# frontplatine_v0_2_310121.net
KiCad netlist of a schematic drawn in EAGLE
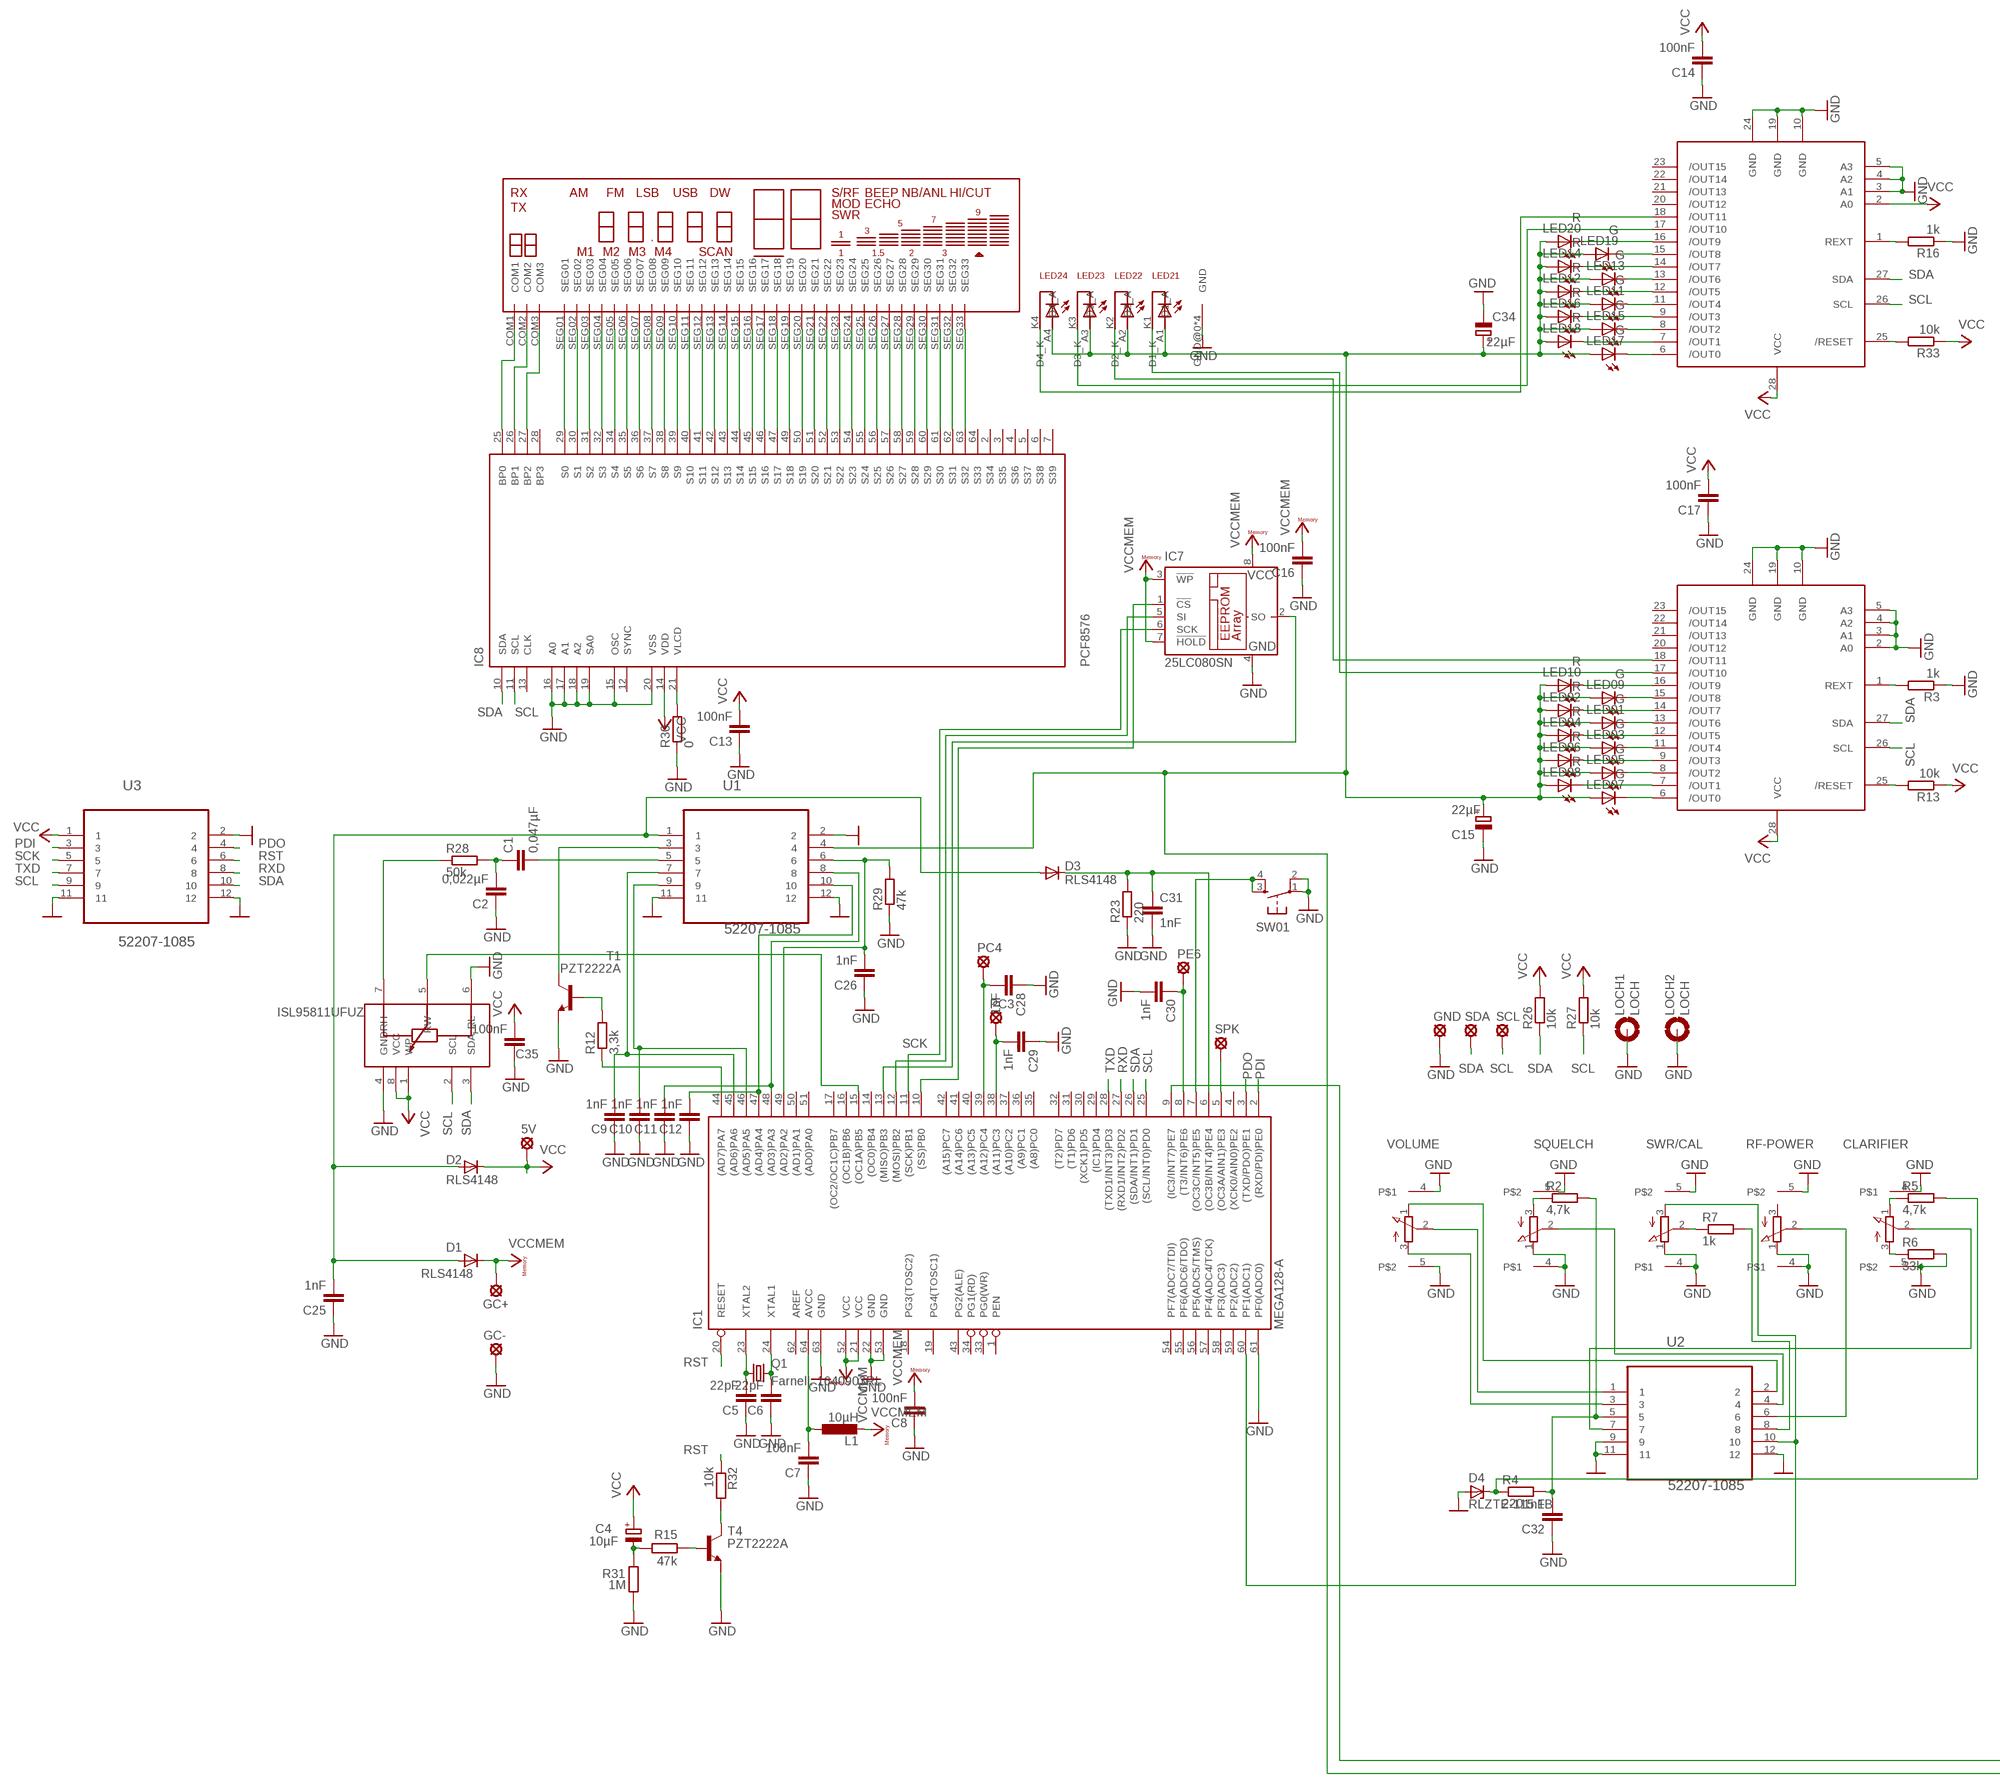
[diagram p0: schematic, sheet 1, part 1 of 2]
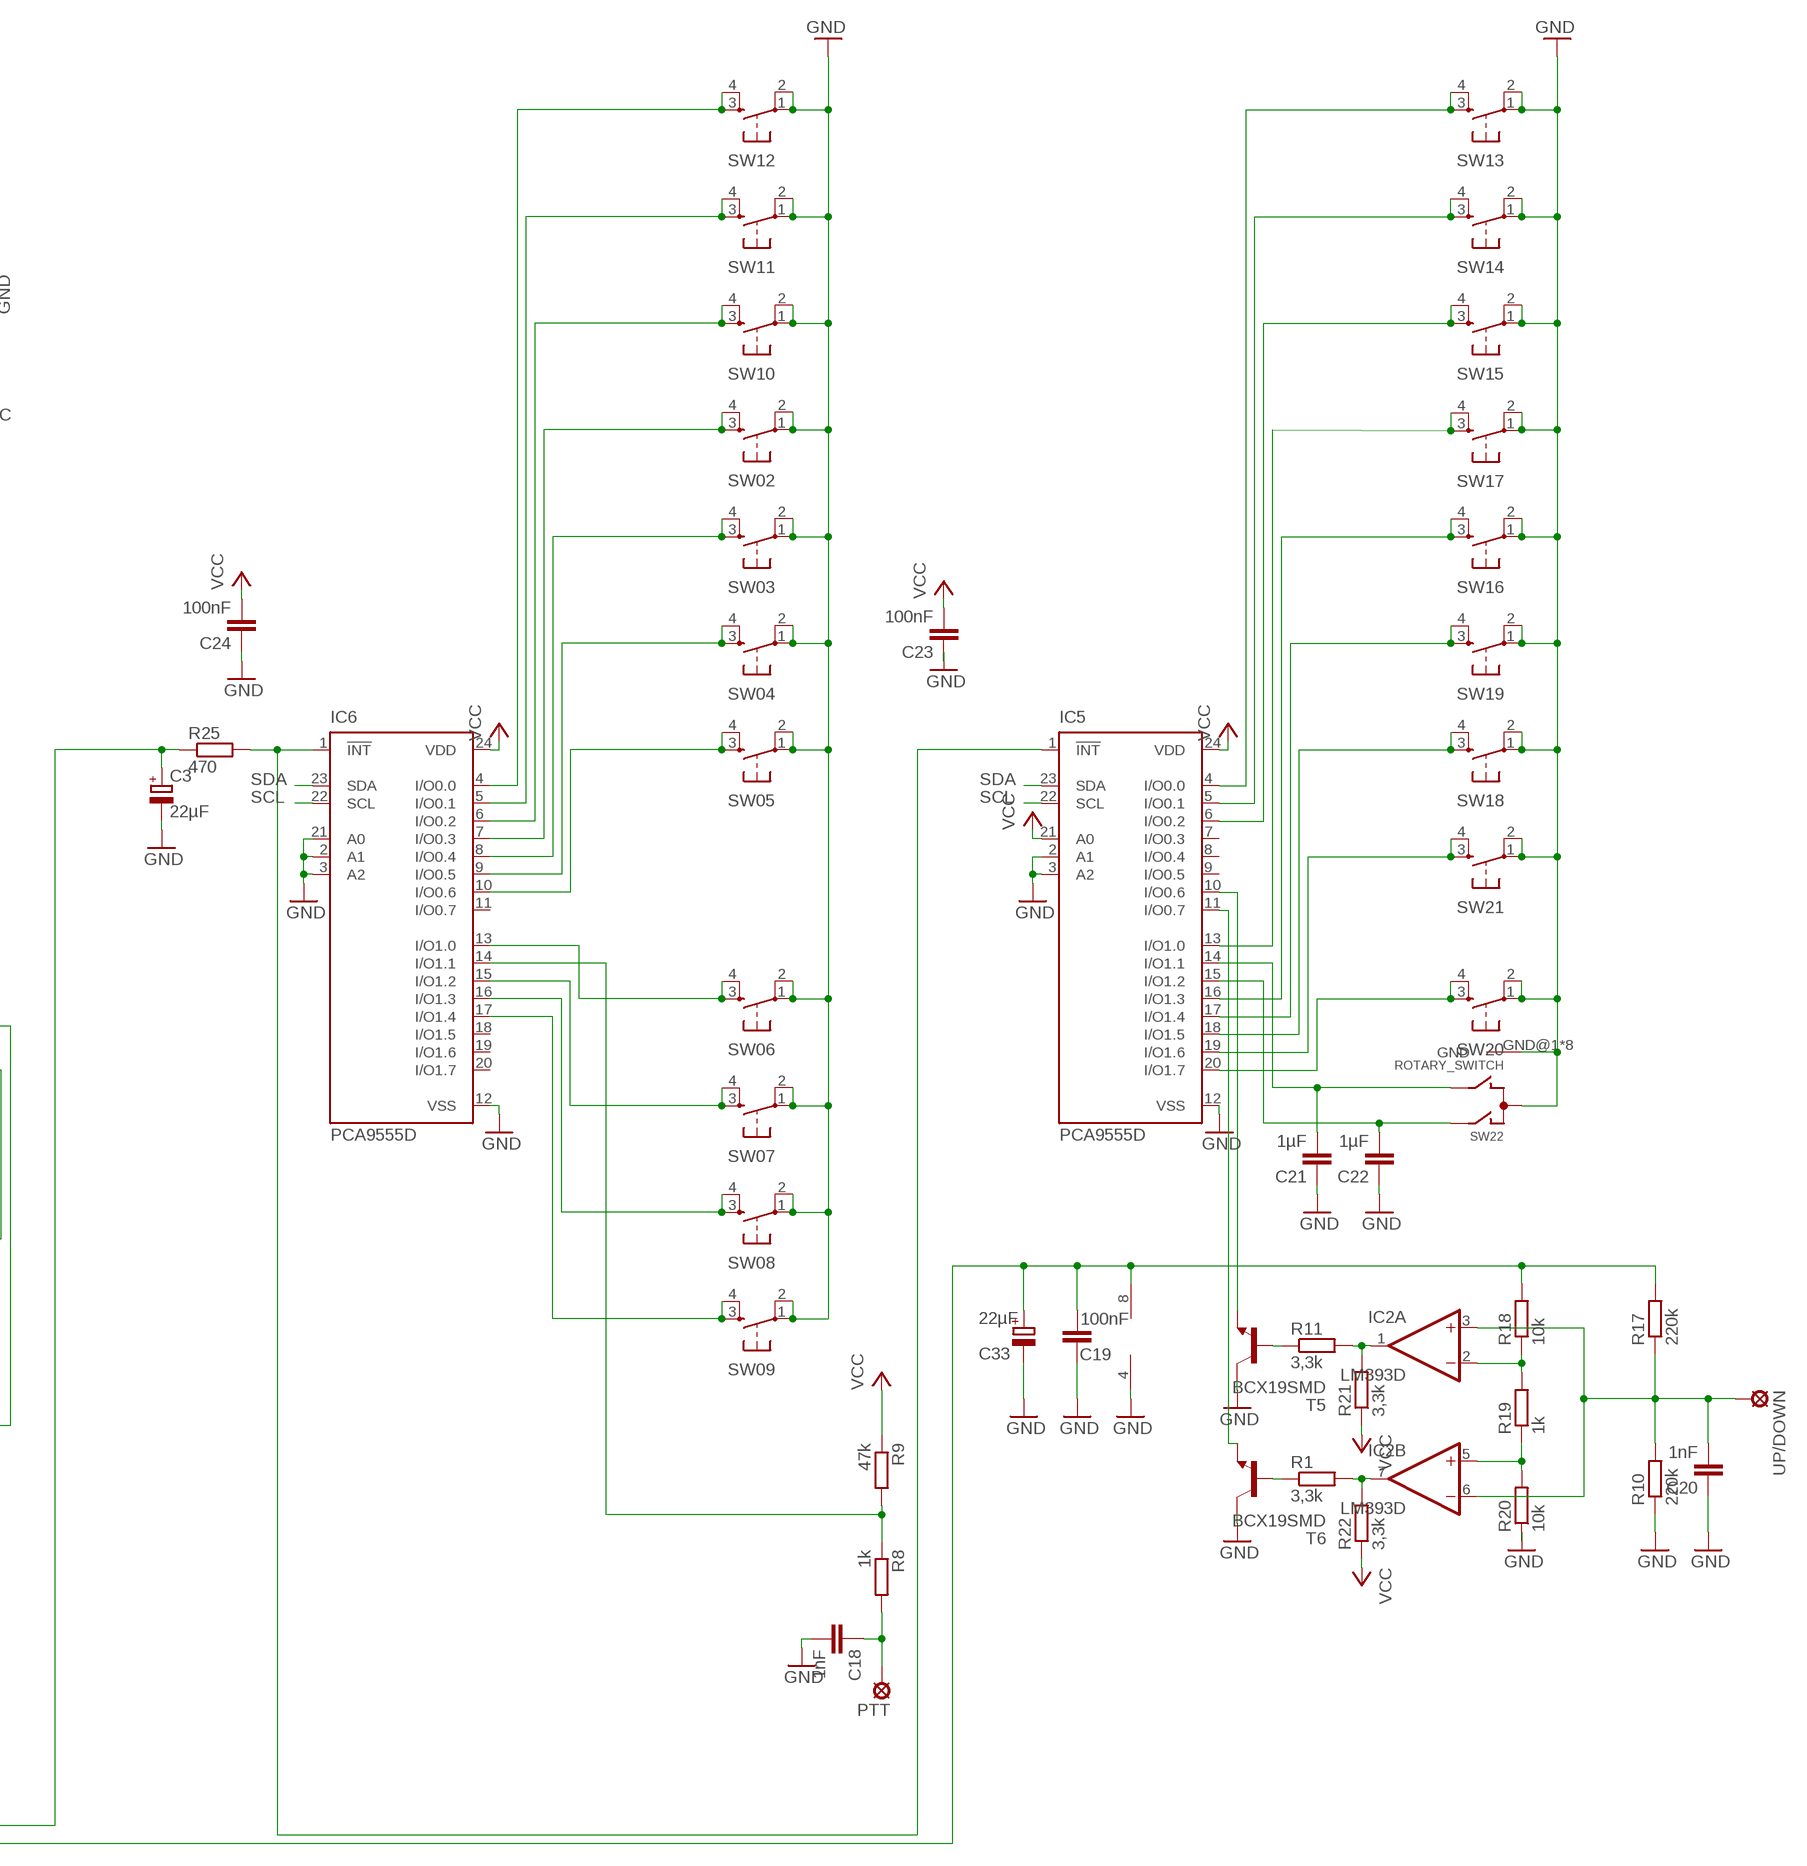
[diagram p1: schematic, sheet 1, part 2 of 2]

(export (version "E")
  (design (tool "Eeschema 10.0.6"))
  (components
    (comp (ref "5V")
      (value "SE11")
      (footprint "eagle-import:SE11")
      (libsource (lib "eagle-import") (part "SE11"))
    )
    (comp (ref "C1")
      (value "0,047µF")
      (footprint "eagle-import:C1206")
      (libsource (lib "eagle-import") (part "C-EUC1206"))
    )
    (comp (ref "C2")
      (value "0,022µF")
      (footprint "eagle-import:C1206")
      (libsource (lib "eagle-import") (part "resistor_C-EUC1206"))
    )
    (comp (ref "C3")
      (value "22µF")
      (footprint "eagle-import:CT3216")
      (libsource (lib "eagle-import") (part "CPOL-EUCT3216"))
    )
    (comp (ref "C4")
      (value "10µF")
      (footprint "eagle-import:CT3216")
      (libsource (lib "eagle-import") (part "CPOL-EUCT3216"))
    )
    (comp (ref "C5")
      (value "22pF")
      (footprint "eagle-import:C1206")
      (libsource (lib "eagle-import") (part "resistor_C-EUC1206"))
    )
    (comp (ref "C6")
      (value "22pF")
      (footprint "eagle-import:C1206")
      (libsource (lib "eagle-import") (part "resistor_C-EUC1206"))
    )
    (comp (ref "C7")
      (value "100nF")
      (footprint "eagle-import:C1206")
      (libsource (lib "eagle-import") (part "resistor_C-EUC1206"))
    )
    (comp (ref "C8")
      (value "100nF")
      (footprint "eagle-import:C1206")
      (libsource (lib "eagle-import") (part "resistor_C-EUC1206"))
    )
    (comp (ref "C9")
      (value "1nF")
      (footprint "eagle-import:C1206")
      (libsource (lib "eagle-import") (part "resistor_C-EUC1206"))
    )
    (comp (ref "C10")
      (value "1nF")
      (footprint "eagle-import:C1206")
      (libsource (lib "eagle-import") (part "resistor_C-EUC1206"))
    )
    (comp (ref "C11")
      (value "1nF")
      (footprint "eagle-import:C1206")
      (libsource (lib "eagle-import") (part "resistor_C-EUC1206"))
    )
    (comp (ref "C12")
      (value "1nF")
      (footprint "eagle-import:C1206")
      (libsource (lib "eagle-import") (part "resistor_C-EUC1206"))
    )
    (comp (ref "C13")
      (value "100nF")
      (footprint "eagle-import:C1206")
      (libsource (lib "eagle-import") (part "resistor_C-EUC1206"))
    )
    (comp (ref "C14")
      (value "100nF")
      (footprint "eagle-import:C1206")
      (libsource (lib "eagle-import") (part "resistor_C-EUC1206"))
    )
    (comp (ref "C15")
      (value "22µF")
      (footprint "eagle-import:CT3216")
      (libsource (lib "eagle-import") (part "CPOL-EUCT3216"))
    )
    (comp (ref "C16")
      (value "100nF")
      (footprint "eagle-import:C1206")
      (libsource (lib "eagle-import") (part "resistor_C-EUC1206"))
    )
    (comp (ref "C17")
      (value "100nF")
      (footprint "eagle-import:C1206")
      (libsource (lib "eagle-import") (part "resistor_C-EUC1206"))
    )
    (comp (ref "C18")
      (value "1nF")
      (footprint "eagle-import:C1206")
      (libsource (lib "eagle-import") (part "resistor_C-EUC1206"))
    )
    (comp (ref "C19")
      (value "100nF")
      (footprint "eagle-import:C1206")
      (libsource (lib "eagle-import") (part "resistor_C-EUC1206"))
    )
    (comp (ref "C20")
      (value "1nF")
      (footprint "eagle-import:C1206")
      (libsource (lib "eagle-import") (part "resistor_C-EUC1206"))
    )
    (comp (ref "C21")
      (value "1µF")
      (footprint "eagle-import:C1206")
      (libsource (lib "eagle-import") (part "resistor_C-EUC1206"))
    )
    (comp (ref "C22")
      (value "1µF")
      (footprint "eagle-import:C1206")
      (libsource (lib "eagle-import") (part "resistor_C-EUC1206"))
    )
    (comp (ref "C23")
      (value "100nF")
      (footprint "eagle-import:C1206")
      (libsource (lib "eagle-import") (part "resistor_C-EUC1206"))
    )
    (comp (ref "C24")
      (value "100nF")
      (footprint "eagle-import:C1206")
      (libsource (lib "eagle-import") (part "resistor_C-EUC1206"))
    )
    (comp (ref "C25")
      (value "1nF")
      (footprint "eagle-import:C1206")
      (libsource (lib "eagle-import") (part "resistor_C-EUC1206"))
    )
    (comp (ref "C26")
      (value "1nF")
      (footprint "eagle-import:C1206")
      (libsource (lib "eagle-import") (part "resistor_C-EUC1206"))
    )
    (comp (ref "C28")
      (value "1nF")
      (footprint "eagle-import:C1206")
      (libsource (lib "eagle-import") (part "resistor_C-EUC1206"))
    )
    (comp (ref "C29")
      (value "1nF")
      (footprint "eagle-import:C1206")
      (libsource (lib "eagle-import") (part "resistor_C-EUC1206"))
    )
    (comp (ref "C30")
      (value "1nF")
      (footprint "eagle-import:C1206")
      (libsource (lib "eagle-import") (part "resistor_C-EUC1206"))
    )
    (comp (ref "C31")
      (value "1nF")
      (footprint "eagle-import:C1206")
      (libsource (lib "eagle-import") (part "resistor_C-EUC1206"))
    )
    (comp (ref "C32")
      (value "1nF")
      (footprint "eagle-import:C1206")
      (libsource (lib "eagle-import") (part "resistor_C-EUC1206"))
    )
    (comp (ref "C33")
      (value "22µF")
      (footprint "eagle-import:CT3216")
      (libsource (lib "eagle-import") (part "CPOL-EUCT3216"))
    )
    (comp (ref "C34")
      (value "22µF")
      (footprint "eagle-import:CT3216")
      (libsource (lib "eagle-import") (part "CPOL-EUCT3216"))
    )
    (comp (ref "C35")
      (value "100nF")
      (footprint "eagle-import:C1206")
      (libsource (lib "eagle-import") (part "resistor_C-EUC1206"))
    )
    (comp (ref "CLARIFIER")
      (value "POTI")
      (footprint "eagle-import:POTI")
      (libsource (lib "eagle-import") (part "POTI"))
    )
    (comp (ref "D1")
      (value "RLS4148")
      (footprint "eagle-import:SOD80C")
      (libsource (lib "eagle-import") (part "DIODE-SOD80C"))
    )
    (comp (ref "D2")
      (value "RLS4148")
      (footprint "eagle-import:SOD80C")
      (libsource (lib "eagle-import") (part "DIODE-SOD80C"))
    )
    (comp (ref "D3")
      (value "RLS4148")
      (footprint "eagle-import:SOD80C")
      (libsource (lib "eagle-import") (part "DIODE-SOD80C"))
    )
    (comp (ref "D4")
      (value "RLZTE-115.1B")
      (footprint "eagle-import:SOD80C")
      (libsource (lib "eagle-import") (part "ZENER-DIODESOD80C"))
    )
    (comp (ref "DISPLAY1")
      (value "DISPLAY")
      (footprint "eagle-import:DISPLAY")
      (libsource (lib "eagle-import") (part "DISPLAY"))
    )
    (comp (ref "GC+")
      (value "SE11")
      (footprint "eagle-import:SE11")
      (libsource (lib "eagle-import") (part "SE11"))
    )
    (comp (ref "GC-")
      (value "SE11")
      (footprint "eagle-import:SE11")
      (libsource (lib "eagle-import") (part "SE11"))
    )
    (comp (ref "GND")
      (value "SE11")
      (footprint "eagle-import:SE11")
      (libsource (lib "eagle-import") (part "SE11"))
    )
    (comp (ref "IC1")
      (value "MEGA128-A")
      (footprint "eagle-import:TQFP64")
      (fields (field (name "MPN") "ATMEGA128-16AU"))
      (libsource (lib "eagle-import") (part "MEGA128-A"))
    )
    (comp (ref "IC2")
      (value "LM393D")
      (footprint "eagle-import:SO08")
      (libsource (lib "eagle-import") (part "LM393D"))
    )
    (comp (ref "IC3")
      (value "TLC59116")
      (footprint "eagle-import:TSSOP28")
      (libsource (lib "eagle-import") (part "TLC59116"))
    )
    (comp (ref "IC4")
      (value "TLC59116")
      (footprint "eagle-import:TSSOP28")
      (libsource (lib "eagle-import") (part "TLC59116"))
    )
    (comp (ref "IC5")
      (value "PCA9555D")
      (footprint "eagle-import:SO24")
      (fields (field (name "MPN") "PCA9555DW"))
      (libsource (lib "eagle-import") (part "PCA9555D"))
    )
    (comp (ref "IC6")
      (value "PCA9555D")
      (footprint "eagle-import:SO24")
      (fields (field (name "MPN") "PCA9555DW"))
      (libsource (lib "eagle-import") (part "PCA9555D"))
    )
    (comp (ref "IC7")
      (value "25LC080SN")
      (footprint "eagle-import:SO-08")
      (fields
        (field (name "MF") "MICROCHIP")
        (field (name "MPN") "25LC080/SN")
        (field (name "MPN_1") "25LC080/SN")
        (field (name "OC_FARNELL") "1137302")
        (field (name "OC_NEWARK") "96K4092")
      )
      (libsource (lib "eagle-import") (part "25SNLC080"))
    )
    (comp (ref "IC8")
      (value "PCF8576")
      (footprint "eagle-import:LQFP-ST-64-2")
      (libsource (lib "eagle-import") (part "PCF8576"))
    )
    (comp (ref "IC9")
      (value "ISL95811UFUZ")
      (footprint "eagle-import:MSOP8")
      (libsource (lib "eagle-import") (part "ISL95811UFUZ"))
    )
    (comp (ref "L1")
      (value "10µH")
      (footprint "eagle-import:L1812")
      (libsource (lib "eagle-import") (part "L-EUL1812"))
    )
    (comp (ref "LED01")
      (value "G")
      (footprint "eagle-import:CHIPLED_1206")
      (libsource (lib "eagle-import") (part "LEDCHIPLED_1206"))
    )
    (comp (ref "LED02")
      (value "R")
      (footprint "eagle-import:CHIPLED_1206")
      (libsource (lib "eagle-import") (part "LEDCHIPLED_1206"))
    )
    (comp (ref "LED03")
      (value "G")
      (footprint "eagle-import:CHIPLED_1206")
      (libsource (lib "eagle-import") (part "LEDCHIPLED_1206"))
    )
    (comp (ref "LED04")
      (value "R")
      (footprint "eagle-import:CHIPLED_1206")
      (libsource (lib "eagle-import") (part "LEDCHIPLED_1206"))
    )
    (comp (ref "LED05")
      (value "G")
      (footprint "eagle-import:CHIPLED_1206")
      (libsource (lib "eagle-import") (part "LEDCHIPLED_1206"))
    )
    (comp (ref "LED06")
      (value "R")
      (footprint "eagle-import:CHIPLED_1206")
      (libsource (lib "eagle-import") (part "LEDCHIPLED_1206"))
    )
    (comp (ref "LED07")
      (value "G")
      (footprint "eagle-import:CHIPLED_1206")
      (libsource (lib "eagle-import") (part "LEDCHIPLED_1206"))
    )
    (comp (ref "LED08")
      (value "R")
      (footprint "eagle-import:CHIPLED_1206")
      (libsource (lib "eagle-import") (part "LEDCHIPLED_1206"))
    )
    (comp (ref "LED09")
      (value "G")
      (footprint "eagle-import:CHIPLED_1206")
      (libsource (lib "eagle-import") (part "LEDCHIPLED_1206"))
    )
    (comp (ref "LED10")
      (value "R")
      (footprint "eagle-import:CHIPLED_1206")
      (libsource (lib "eagle-import") (part "LEDCHIPLED_1206"))
    )
    (comp (ref "LED11")
      (value "G")
      (footprint "eagle-import:CHIPLED_1206")
      (libsource (lib "eagle-import") (part "LEDCHIPLED_1206"))
    )
    (comp (ref "LED12")
      (value "R")
      (footprint "eagle-import:CHIPLED_1206")
      (libsource (lib "eagle-import") (part "LEDCHIPLED_1206"))
    )
    (comp (ref "LED13")
      (value "G")
      (footprint "eagle-import:CHIPLED_1206")
      (libsource (lib "eagle-import") (part "LEDCHIPLED_1206"))
    )
    (comp (ref "LED14")
      (value "R")
      (footprint "eagle-import:CHIPLED_1206")
      (libsource (lib "eagle-import") (part "LEDCHIPLED_1206"))
    )
    (comp (ref "LED15")
      (value "G")
      (footprint "eagle-import:CHIPLED_1206")
      (libsource (lib "eagle-import") (part "LEDCHIPLED_1206"))
    )
    (comp (ref "LED16")
      (value "R")
      (footprint "eagle-import:CHIPLED_1206")
      (libsource (lib "eagle-import") (part "LEDCHIPLED_1206"))
    )
    (comp (ref "LED17")
      (value "G")
      (footprint "eagle-import:CHIPLED_1206")
      (libsource (lib "eagle-import") (part "LEDCHIPLED_1206"))
    )
    (comp (ref "LED18")
      (value "R")
      (footprint "eagle-import:CHIPLED_1206")
      (libsource (lib "eagle-import") (part "LEDCHIPLED_1206"))
    )
    (comp (ref "LED19")
      (value "G")
      (footprint "eagle-import:CHIPLED_1206")
      (libsource (lib "eagle-import") (part "LEDCHIPLED_1206"))
    )
    (comp (ref "LED20")
      (value "R")
      (footprint "eagle-import:CHIPLED_1206")
      (libsource (lib "eagle-import") (part "LEDCHIPLED_1206"))
    )
    (comp (ref "LOCH1")
      (value "LOCH")
      (footprint "eagle-import:LOCH")
      (libsource (lib "eagle-import") (part "LOCH"))
    )
    (comp (ref "LOCH2")
      (value "LOCH")
      (footprint "eagle-import:LOCH")
      (libsource (lib "eagle-import") (part "LOCH"))
    )
    (comp (ref "PC3")
      (value "SE11")
      (footprint "eagle-import:SE11")
      (libsource (lib "eagle-import") (part "SE11"))
    )
    (comp (ref "PC4")
      (value "SE11")
      (footprint "eagle-import:SE11")
      (libsource (lib "eagle-import") (part "SE11"))
    )
    (comp (ref "PE6")
      (value "SE11")
      (footprint "eagle-import:SE11")
      (libsource (lib "eagle-import") (part "SE11"))
    )
    (comp (ref "PTT")
      (value "SE11")
      (footprint "eagle-import:SE11")
      (libsource (lib "eagle-import") (part "SE11"))
    )
    (comp (ref "Q1")
      (value "Farnell: 1640903RL")
      (footprint "eagle-import:HC49UP")
      (libsource (lib "eagle-import") (part "CRYSTALHC49UP"))
    )
    (comp (ref "R1")
      (value "3,3k")
      (footprint "eagle-import:R1206")
      (libsource (lib "eagle-import") (part "resistor_R-EU_R1206"))
    )
    (comp (ref "R2")
      (value "4,7k")
      (footprint "eagle-import:R1206")
      (libsource (lib "eagle-import") (part "resistor_R-EU_R1206"))
    )
    (comp (ref "R3")
      (value "1k")
      (footprint "eagle-import:R1206")
      (libsource (lib "eagle-import") (part "R-EU_R1206"))
    )
    (comp (ref "R4")
      (value "220")
      (footprint "eagle-import:R1206")
      (libsource (lib "eagle-import") (part "resistor_R-EU_R1206"))
    )
    (comp (ref "R5")
      (value "4,7k")
      (footprint "eagle-import:R1206")
      (libsource (lib "eagle-import") (part "resistor_R-EU_R1206"))
    )
    (comp (ref "R6")
      (value "33k")
      (footprint "eagle-import:R1206")
      (libsource (lib "eagle-import") (part "resistor_R-EU_R1206"))
    )
    (comp (ref "R7")
      (value "1k")
      (footprint "eagle-import:R1206")
      (libsource (lib "eagle-import") (part "resistor_R-EU_R1206"))
    )
    (comp (ref "R8")
      (value "1k")
      (footprint "eagle-import:R1206")
      (libsource (lib "eagle-import") (part "resistor_R-EU_R1206"))
    )
    (comp (ref "R9")
      (value "47k")
      (footprint "eagle-import:R1206")
      (libsource (lib "eagle-import") (part "resistor_R-EU_R1206"))
    )
    (comp (ref "R10")
      (value "220k")
      (footprint "eagle-import:R1206")
      (libsource (lib "eagle-import") (part "resistor_R-EU_R1206"))
    )
    (comp (ref "R11")
      (value "3,3k")
      (footprint "eagle-import:R1206")
      (libsource (lib "eagle-import") (part "resistor_R-EU_R1206"))
    )
    (comp (ref "R12")
      (value "3,3k")
      (footprint "eagle-import:R1206")
      (libsource (lib "eagle-import") (part "resistor_R-EU_R1206"))
    )
    (comp (ref "R13")
      (value "10k")
      (footprint "eagle-import:R1206")
      (libsource (lib "eagle-import") (part "resistor_R-EU_R1206"))
    )
    (comp (ref "R15")
      (value "47k")
      (footprint "eagle-import:R1206")
      (libsource (lib "eagle-import") (part "resistor_R-EU_R1206"))
    )
    (comp (ref "R16")
      (value "1k")
      (footprint "eagle-import:R1206")
      (libsource (lib "eagle-import") (part "R-EU_R1206"))
    )
    (comp (ref "R17")
      (value "220k")
      (footprint "eagle-import:R1206")
      (libsource (lib "eagle-import") (part "resistor_R-EU_R1206"))
    )
    (comp (ref "R18")
      (value "10k")
      (footprint "eagle-import:R1206")
      (libsource (lib "eagle-import") (part "resistor_R-EU_R1206"))
    )
    (comp (ref "R19")
      (value "1k")
      (footprint "eagle-import:R1206")
      (libsource (lib "eagle-import") (part "resistor_R-EU_R1206"))
    )
    (comp (ref "R20")
      (value "10k")
      (footprint "eagle-import:R1206")
      (libsource (lib "eagle-import") (part "resistor_R-EU_R1206"))
    )
    (comp (ref "R21")
      (value "3,3k")
      (footprint "eagle-import:R1206")
      (libsource (lib "eagle-import") (part "resistor_R-EU_R1206"))
    )
    (comp (ref "R22")
      (value "3,3k")
      (footprint "eagle-import:R1206")
      (libsource (lib "eagle-import") (part "resistor_R-EU_R1206"))
    )
    (comp (ref "R23")
      (value "220")
      (footprint "eagle-import:R1206")
      (libsource (lib "eagle-import") (part "resistor_R-EU_R1206"))
    )
    (comp (ref "R25")
      (value "470")
      (footprint "eagle-import:R1206")
      (libsource (lib "eagle-import") (part "resistor_R-EU_R1206"))
    )
    (comp (ref "R26")
      (value "10k")
      (footprint "eagle-import:R1206")
      (libsource (lib "eagle-import") (part "resistor_R-EU_R1206"))
    )
    (comp (ref "R27")
      (value "10k")
      (footprint "eagle-import:R1206")
      (libsource (lib "eagle-import") (part "resistor_R-EU_R1206"))
    )
    (comp (ref "R28")
      (value "50k")
      (footprint "eagle-import:R1206")
      (libsource (lib "eagle-import") (part "resistor_R-EU_R1206"))
    )
    (comp (ref "R29")
      (value "47k")
      (footprint "eagle-import:R1206")
      (libsource (lib "eagle-import") (part "resistor_R-EU_R1206"))
    )
    (comp (ref "R30")
      (value "0")
      (footprint "eagle-import:R1206")
      (libsource (lib "eagle-import") (part "resistor_R-EU_R1206"))
    )
    (comp (ref "R31")
      (value "1M")
      (footprint "eagle-import:R1206")
      (libsource (lib "eagle-import") (part "resistor_R-EU_R1206"))
    )
    (comp (ref "R32")
      (value "10k")
      (footprint "eagle-import:R1206")
      (libsource (lib "eagle-import") (part "resistor_R-EU_R1206"))
    )
    (comp (ref "R33")
      (value "10k")
      (footprint "eagle-import:R1206")
      (libsource (lib "eagle-import") (part "resistor_R-EU_R1206"))
    )
    (comp (ref "RF-POWER")
      (value "POTI")
      (footprint "eagle-import:POTI")
      (libsource (lib "eagle-import") (part "POTI"))
    )
    (comp (ref "SCL")
      (value "SE11")
      (footprint "eagle-import:SE11")
      (libsource (lib "eagle-import") (part "SE11"))
    )
    (comp (ref "SDA")
      (value "SE11")
      (footprint "eagle-import:SE11")
      (libsource (lib "eagle-import") (part "SE11"))
    )
    (comp (ref "SPK")
      (value "SE11")
      (footprint "eagle-import:SE11")
      (libsource (lib "eagle-import") (part "SE11"))
    )
    (comp (ref "SQUELCH")
      (value "POTI")
      (footprint "eagle-import:POTI")
      (libsource (lib "eagle-import") (part "POTI"))
    )
    (comp (ref "SW01")
      (value "TASTER")
      (footprint "eagle-import:TASTER")
      (libsource (lib "eagle-import") (part "TASTER"))
    )
    (comp (ref "SW02")
      (value "TASTER")
      (footprint "eagle-import:TASTER")
      (libsource (lib "eagle-import") (part "TASTER"))
    )
    (comp (ref "SW03")
      (value "TASTER")
      (footprint "eagle-import:TASTER")
      (libsource (lib "eagle-import") (part "TASTER"))
    )
    (comp (ref "SW04")
      (value "TASTER")
      (footprint "eagle-import:TASTER")
      (libsource (lib "eagle-import") (part "TASTER"))
    )
    (comp (ref "SW05")
      (value "TASTER")
      (footprint "eagle-import:TASTER")
      (libsource (lib "eagle-import") (part "TASTER"))
    )
    (comp (ref "SW06")
      (value "TASTER")
      (footprint "eagle-import:TASTER")
      (libsource (lib "eagle-import") (part "TASTER"))
    )
    (comp (ref "SW07")
      (value "TASTER")
      (footprint "eagle-import:TASTER")
      (libsource (lib "eagle-import") (part "TASTER"))
    )
    (comp (ref "SW08")
      (value "TASTER")
      (footprint "eagle-import:TASTER")
      (libsource (lib "eagle-import") (part "TASTER"))
    )
    (comp (ref "SW09")
      (value "TASTER")
      (footprint "eagle-import:TASTER")
      (libsource (lib "eagle-import") (part "TASTER"))
    )
    (comp (ref "SW10")
      (value "TASTER")
      (footprint "eagle-import:TASTER")
      (libsource (lib "eagle-import") (part "TASTER"))
    )
    (comp (ref "SW11")
      (value "TASTER")
      (footprint "eagle-import:TASTER")
      (libsource (lib "eagle-import") (part "TASTER"))
    )
    (comp (ref "SW12")
      (value "TASTER")
      (footprint "eagle-import:TASTER")
      (libsource (lib "eagle-import") (part "TASTER"))
    )
    (comp (ref "SW13")
      (value "TASTER")
      (footprint "eagle-import:TASTER")
      (libsource (lib "eagle-import") (part "TASTER"))
    )
    (comp (ref "SW14")
      (value "TASTER")
      (footprint "eagle-import:TASTER")
      (libsource (lib "eagle-import") (part "TASTER"))
    )
    (comp (ref "SW15")
      (value "TASTER")
      (footprint "eagle-import:TASTER")
      (libsource (lib "eagle-import") (part "TASTER"))
    )
    (comp (ref "SW16")
      (value "TASTER")
      (footprint "eagle-import:TASTER")
      (libsource (lib "eagle-import") (part "TASTER"))
    )
    (comp (ref "SW17")
      (value "TASTER")
      (footprint "eagle-import:TASTER")
      (libsource (lib "eagle-import") (part "TASTER"))
    )
    (comp (ref "SW18")
      (value "TASTER")
      (footprint "eagle-import:TASTER")
      (libsource (lib "eagle-import") (part "TASTER"))
    )
    (comp (ref "SW19")
      (value "TASTER")
      (footprint "eagle-import:TASTER")
      (libsource (lib "eagle-import") (part "TASTER"))
    )
    (comp (ref "SW20")
      (value "TASTER")
      (footprint "eagle-import:TASTER")
      (libsource (lib "eagle-import") (part "TASTER"))
    )
    (comp (ref "SW21")
      (value "TASTER")
      (footprint "eagle-import:TASTER")
      (libsource (lib "eagle-import") (part "TASTER"))
    )
    (comp (ref "SW22")
      (value "ROTARY_SWITCH")
      (footprint "eagle-import:ROTARY_SWITCH")
      (libsource (lib "eagle-import") (part "ROTARY_SWITCH"))
    )
    (comp (ref "SWR/CAL")
      (value "POTI")
      (footprint "eagle-import:POTI")
      (libsource (lib "eagle-import") (part "POTI"))
    )
    (comp (ref "T1")
      (value "PZT2222A")
      (footprint "eagle-import:SOT223")
      (libsource (lib "eagle-import") (part "-NPN-SOT223PZT2222A"))
    )
    (comp (ref "T4")
      (value "PZT2222A")
      (footprint "eagle-import:SOT223")
      (libsource (lib "eagle-import") (part "-NPN-SOT223PZT2222A"))
    )
    (comp (ref "T5")
      (value "BCX19SMD")
      (footprint "eagle-import:SOT23-BEC")
      (libsource (lib "eagle-import") (part "BCX19SMD"))
    )
    (comp (ref "T6")
      (value "BCX19SMD")
      (footprint "eagle-import:SOT23-BEC")
      (libsource (lib "eagle-import") (part "BCX19SMD"))
    )
    (comp (ref "U1")
      (value "52207-1085")
      (footprint "eagle-import:MOLEX_52207-1085")
      (fields
        (field (name "MPN") "52207-1085")
        (field (name "OC_FARNELL") "1079938")
        (field (name "OC_NEWARK") "58J9503")
        (field (name "PACKAGE") "SOCKET FPC, SMT, 1MM, 10 WAY")
      )
      (libsource (lib "eagle-import") (part "52207-1085"))
    )
    (comp (ref "U2")
      (value "52207-1085")
      (footprint "eagle-import:MOLEX_52207-1085")
      (fields
        (field (name "MPN") "52207-1085")
        (field (name "OC_FARNELL") "1079938")
        (field (name "OC_NEWARK") "58J9503")
        (field (name "PACKAGE") "SOCKET FPC, SMT, 1MM, 10 WAY")
      )
      (libsource (lib "eagle-import") (part "52207-1085"))
    )
    (comp (ref "U3")
      (value "52207-1085")
      (footprint "eagle-import:MOLEX_52207-1085")
      (libsource (lib "eagle-import") (part "52207-1085"))
    )
    (comp (ref "UP/DOWN")
      (value "SE11")
      (footprint "eagle-import:SE11")
      (libsource (lib "eagle-import") (part "SE11"))
    )
    (comp (ref "VOLUME")
      (value "POTI")
      (footprint "eagle-import:POTI")
      (libsource (lib "eagle-import") (part "POTI"))
    )
  )
  (nets
    (net (code "1") (name "/PDI") (class "Default")
      (node (ref "IC1") (pin "2") (pinfunction "(RXD/PDI)PE0_2") (pintype "bidirectional"))
      (node (ref "U3") (pin "3") (pinfunction "3_3") (pintype "passive"))
    )
    (net (code "2") (name "/PDO") (class "Default")
      (node (ref "IC1") (pin "3") (pinfunction "(TXD/PDO)PE1_3") (pintype "bidirectional"))
      (node (ref "U3") (pin "4") (pinfunction "4_4") (pintype "passive"))
    )
    (net (code "3") (name "/RST") (class "Default")
      (node (ref "IC1") (pin "20") (pinfunction "RESET_20") (pintype "input"))
      (node (ref "R32") (pin "1") (pinfunction "1_1") (pintype "passive"))
      (node (ref "U3") (pin "6") (pinfunction "6_6") (pintype "passive"))
    )
    (net (code "4") (name "/RXD") (class "Default")
      (node (ref "IC1") (pin "27") (pinfunction "(RXD1/INT2)PD2_27") (pintype "bidirectional"))
      (node (ref "U3") (pin "8") (pinfunction "8_8") (pintype "passive"))
    )
    (net (code "5") (name "/SCK") (class "Default")
      (node (ref "IC1") (pin "11") (pinfunction "(SCK)PB1_11") (pintype "bidirectional"))
      (node (ref "IC7") (pin "6") (pinfunction "SCK_6") (pintype "input"))
      (node (ref "U3") (pin "5") (pinfunction "5_5") (pintype "passive"))
    )
    (net (code "6") (name "/SCL") (class "Default")
      (node (ref "IC1") (pin "25") (pinfunction "(SCL/INT0)PD0_25") (pintype "bidirectional"))
      (node (ref "IC3") (pin "26") (pinfunction "SCL_26") (pintype "bidirectional"))
      (node (ref "IC4") (pin "26") (pinfunction "SCL_26") (pintype "bidirectional"))
      (node (ref "IC5") (pin "22") (pinfunction "SCL_22") (pintype "input"))
      (node (ref "IC6") (pin "22") (pinfunction "SCL_22") (pintype "input"))
      (node (ref "IC8") (pin "11") (pinfunction "SCL_11") (pintype "input"))
      (node (ref "IC9") (pin "2") (pinfunction "SCL_2") (pintype "bidirectional"))
      (node (ref "R27") (pin "1") (pinfunction "1_1") (pintype "passive"))
      (node (ref "SCL") (pin "MP") (pinfunction "MP_MP") (pintype "passive"))
      (node (ref "U3") (pin "9") (pinfunction "9_9") (pintype "passive"))
    )
    (net (code "7") (name "/SDA") (class "Default")
      (node (ref "IC1") (pin "26") (pinfunction "(SDA/INT1)PD1_26") (pintype "bidirectional"))
      (node (ref "IC3") (pin "27") (pinfunction "SDA_27") (pintype "bidirectional"))
      (node (ref "IC4") (pin "27") (pinfunction "SDA_27") (pintype "bidirectional"))
      (node (ref "IC5") (pin "23") (pinfunction "SDA_23") (pintype "bidirectional"))
      (node (ref "IC6") (pin "23") (pinfunction "SDA_23") (pintype "bidirectional"))
      (node (ref "IC8") (pin "10") (pinfunction "SDA_10") (pintype "bidirectional"))
      (node (ref "IC9") (pin "3") (pinfunction "SDA_3") (pintype "input"))
      (node (ref "R26") (pin "1") (pinfunction "1_1") (pintype "passive"))
      (node (ref "SDA") (pin "MP") (pinfunction "MP_MP") (pintype "passive"))
      (node (ref "U3") (pin "10") (pinfunction "10_10") (pintype "passive"))
    )
    (net (code "8") (name "/TXD") (class "Default")
      (node (ref "IC1") (pin "28") (pinfunction "(TXD1/INT3)PD3_28") (pintype "bidirectional"))
      (node (ref "U3") (pin "7") (pinfunction "7_7") (pintype "passive"))
    )
    (net (code "9") (name "GND") (class "Default")
      (node (ref "C10") (pin "1") (pinfunction "1_1") (pintype "passive"))
      (node (ref "C11") (pin "1") (pinfunction "1_1") (pintype "passive"))
      (node (ref "C12") (pin "1") (pinfunction "1_1") (pintype "passive"))
      (node (ref "C13") (pin "1") (pinfunction "1_1") (pintype "passive"))
      (node (ref "C14") (pin "1") (pinfunction "1_1") (pintype "passive"))
      (node (ref "C15") (pin "-") (pinfunction "-_-") (pintype "passive"))
      (node (ref "C16") (pin "1") (pinfunction "1_1") (pintype "passive"))
      (node (ref "C17") (pin "1") (pinfunction "1_1") (pintype "passive"))
      (node (ref "C18") (pin "2") (pinfunction "2_2") (pintype "passive"))
      (node (ref "C19") (pin "1") (pinfunction "1_1") (pintype "passive"))
      (node (ref "C2") (pin "1") (pinfunction "1_1") (pintype "passive"))
      (node (ref "C20") (pin "1") (pinfunction "1_1") (pintype "passive"))
      (node (ref "C21") (pin "1") (pinfunction "1_1") (pintype "passive"))
      (node (ref "C22") (pin "1") (pinfunction "1_1") (pintype "passive"))
      (node (ref "C23") (pin "1") (pinfunction "1_1") (pintype "passive"))
      (node (ref "C24") (pin "1") (pinfunction "1_1") (pintype "passive"))
      (node (ref "C25") (pin "1") (pinfunction "1_1") (pintype "passive"))
      (node (ref "C26") (pin "1") (pinfunction "1_1") (pintype "passive"))
      (node (ref "C28") (pin "1") (pinfunction "1_1") (pintype "passive"))
      (node (ref "C29") (pin "1") (pinfunction "1_1") (pintype "passive"))
      (node (ref "C3") (pin "-") (pinfunction "-_-") (pintype "passive"))
      (node (ref "C30") (pin "2") (pinfunction "2_2") (pintype "passive"))
      (node (ref "C31") (pin "2") (pinfunction "2_2") (pintype "passive"))
      (node (ref "C32") (pin "1") (pinfunction "1_1") (pintype "passive"))
      (node (ref "C33") (pin "-") (pinfunction "-_-") (pintype "passive"))
      (node (ref "C34") (pin "-") (pinfunction "-_-") (pintype "passive"))
      (node (ref "C35") (pin "1") (pinfunction "1_1") (pintype "passive"))
      (node (ref "C5") (pin "1") (pinfunction "1_1") (pintype "passive"))
      (node (ref "C6") (pin "1") (pinfunction "1_1") (pintype "passive"))
      (node (ref "C7") (pin "1") (pinfunction "1_1") (pintype "passive"))
      (node (ref "C8") (pin "1") (pinfunction "1_1") (pintype "passive"))
      (node (ref "C9") (pin "1") (pinfunction "1_1") (pintype "passive"))
      (node (ref "CLARIFIER") (pin "4") (pinfunction "P$1_4") (pintype "power_in"))
      (node (ref "CLARIFIER") (pin "5") (pinfunction "P$2_5") (pintype "power_in"))
      (node (ref "D4") (pin "A") (pinfunction "A_A") (pintype "passive"))
      (node (ref "DISPLAY1") (pin "GND@0") (pinfunction "GND_GND@0") (pintype "power_in"))
      (node (ref "DISPLAY1") (pin "GND@3") (pinfunction "GND_GND@3") (pintype "power_in"))
      (node (ref "DISPLAY1") (pin "GND@6") (pinfunction "GND_GND@6") (pintype "power_in"))
      (node (ref "DISPLAY1") (pin "GND@7") (pinfunction "GND_GND@7") (pintype "power_in"))
      (node (ref "GC-") (pin "MP") (pinfunction "MP_MP") (pintype "passive"))
      (node (ref "GND") (pin "MP") (pinfunction "MP_MP") (pintype "passive"))
      (node (ref "IC1") (pin "22") (pinfunction "GND_22") (pintype "power_in"))
      (node (ref "IC1") (pin "53") (pinfunction "GND_53") (pintype "power_in"))
      (node (ref "IC1") (pin "61") (pinfunction "PF0(ADC0)_61") (pintype "input"))
      (node (ref "IC1") (pin "63") (pinfunction "GND_63") (pintype "power_in"))
      (node (ref "IC2") (pin "4") (pinfunction "V-_4") (pintype "power_in"))
      (node (ref "IC3") (pin "10") (pinfunction "GND_10") (pintype "bidirectional"))
      (node (ref "IC3") (pin "19") (pinfunction "GND_19") (pintype "bidirectional"))
      (node (ref "IC3") (pin "2") (pinfunction "A0_2") (pintype "bidirectional"))
      (node (ref "IC3") (pin "24") (pinfunction "GND_24") (pintype "bidirectional"))
      (node (ref "IC3") (pin "3") (pinfunction "A1_3") (pintype "bidirectional"))
      (node (ref "IC3") (pin "4") (pinfunction "A2_4") (pintype "bidirectional"))
      (node (ref "IC3") (pin "5") (pinfunction "A3_5") (pintype "bidirectional"))
      (node (ref "IC4") (pin "10") (pinfunction "GND_10") (pintype "bidirectional"))
      (node (ref "IC4") (pin "19") (pinfunction "GND_19") (pintype "bidirectional"))
      (node (ref "IC4") (pin "24") (pinfunction "GND_24") (pintype "bidirectional"))
      (node (ref "IC4") (pin "3") (pinfunction "A1_3") (pintype "bidirectional"))
      (node (ref "IC4") (pin "4") (pinfunction "A2_4") (pintype "bidirectional"))
      (node (ref "IC4") (pin "5") (pinfunction "A3_5") (pintype "bidirectional"))
      (node (ref "IC5") (pin "12") (pinfunction "VSS_12") (pintype "power_in"))
      (node (ref "IC5") (pin "2") (pinfunction "A1_2") (pintype "input"))
      (node (ref "IC5") (pin "3") (pinfunction "A2_3") (pintype "input"))
      (node (ref "IC6") (pin "12") (pinfunction "VSS_12") (pintype "power_in"))
      (node (ref "IC6") (pin "2") (pinfunction "A1_2") (pintype "input"))
      (node (ref "IC6") (pin "21") (pinfunction "A0_21") (pintype "input"))
      (node (ref "IC6") (pin "3") (pinfunction "A2_3") (pintype "input"))
      (node (ref "IC7") (pin "4") (pinfunction "GND_4") (pintype "power_in"))
      (node (ref "IC8") (pin "15") (pinfunction "OSC_15") (pintype "input"))
      (node (ref "IC8") (pin "16") (pinfunction "A0_16") (pintype "input"))
      (node (ref "IC8") (pin "17") (pinfunction "A1_17") (pintype "input"))
      (node (ref "IC8") (pin "18") (pinfunction "A2_18") (pintype "input"))
      (node (ref "IC8") (pin "19") (pinfunction "SA0_19") (pintype "input"))
      (node (ref "IC8") (pin "20") (pinfunction "VSS_20") (pintype "power_in"))
      (node (ref "IC9") (pin "4") (pinfunction "GND_4") (pintype "power_in"))
      (node (ref "IC9") (pin "6") (pinfunction "RL_6") (pintype "bidirectional"))
      (node (ref "LOCH1") (pin "B3,0") (pinfunction "MOUNT_B3,0") (pintype "passive"))
      (node (ref "LOCH2") (pin "B3,0") (pinfunction "MOUNT_B3,0") (pintype "passive"))
      (node (ref "R10") (pin "1") (pinfunction "1_1") (pintype "passive"))
      (node (ref "R16") (pin "1") (pinfunction "1_1") (pintype "passive"))
      (node (ref "R20") (pin "1") (pinfunction "1_1") (pintype "passive"))
      (node (ref "R23") (pin "1") (pinfunction "1_1") (pintype "passive"))
      (node (ref "R29") (pin "1") (pinfunction "1_1") (pintype "passive"))
      (node (ref "R3") (pin "1") (pinfunction "1_1") (pintype "passive"))
      (node (ref "R30") (pin "1") (pinfunction "1_1") (pintype "passive"))
      (node (ref "R31") (pin "2") (pinfunction "2_2") (pintype "passive"))
      (node (ref "R6") (pin "2") (pinfunction "2_2") (pintype "passive"))
      (node (ref "RF-POWER") (pin "1") (pinfunction "E_1") (pintype "passive"))
      (node (ref "RF-POWER") (pin "4") (pinfunction "P$1_4") (pintype "power_in"))
      (node (ref "RF-POWER") (pin "5") (pinfunction "P$2_5") (pintype "power_in"))
      (node (ref "SQUELCH") (pin "1") (pinfunction "E_1") (pintype "passive"))
      (node (ref "SQUELCH") (pin "4") (pinfunction "P$1_4") (pintype "power_in"))
      (node (ref "SQUELCH") (pin "5") (pinfunction "P$2_5") (pintype "power_in"))
      (node (ref "SW01") (pin "1") (pinfunction "1_1") (pintype "passive"))
      (node (ref "SW01") (pin "2") (pinfunction "2_2") (pintype "passive"))
      (node (ref "SW02") (pin "1") (pinfunction "1_1") (pintype "passive"))
      (node (ref "SW02") (pin "2") (pinfunction "2_2") (pintype "passive"))
      (node (ref "SW03") (pin "1") (pinfunction "1_1") (pintype "passive"))
      (node (ref "SW03") (pin "2") (pinfunction "2_2") (pintype "passive"))
      (node (ref "SW04") (pin "1") (pinfunction "1_1") (pintype "passive"))
      (node (ref "SW04") (pin "2") (pinfunction "2_2") (pintype "passive"))
      (node (ref "SW05") (pin "1") (pinfunction "1_1") (pintype "passive"))
      (node (ref "SW05") (pin "2") (pinfunction "2_2") (pintype "passive"))
      (node (ref "SW06") (pin "1") (pinfunction "1_1") (pintype "passive"))
      (node (ref "SW06") (pin "2") (pinfunction "2_2") (pintype "passive"))
      (node (ref "SW07") (pin "1") (pinfunction "1_1") (pintype "passive"))
      (node (ref "SW07") (pin "2") (pinfunction "2_2") (pintype "passive"))
      (node (ref "SW08") (pin "1") (pinfunction "1_1") (pintype "passive"))
      (node (ref "SW08") (pin "2") (pinfunction "2_2") (pintype "passive"))
      (node (ref "SW09") (pin "1") (pinfunction "1_1") (pintype "passive"))
      (node (ref "SW09") (pin "2") (pinfunction "2_2") (pintype "passive"))
      (node (ref "SW10") (pin "1") (pinfunction "1_1") (pintype "passive"))
      (node (ref "SW10") (pin "2") (pinfunction "2_2") (pintype "passive"))
      (node (ref "SW11") (pin "1") (pinfunction "1_1") (pintype "passive"))
      (node (ref "SW11") (pin "2") (pinfunction "2_2") (pintype "passive"))
      (node (ref "SW12") (pin "1") (pinfunction "1_1") (pintype "passive"))
      (node (ref "SW12") (pin "2") (pinfunction "2_2") (pintype "passive"))
      (node (ref "SW13") (pin "1") (pinfunction "1_1") (pintype "passive"))
      (node (ref "SW13") (pin "2") (pinfunction "2_2") (pintype "passive"))
      (node (ref "SW14") (pin "1") (pinfunction "1_1") (pintype "passive"))
      (node (ref "SW14") (pin "2") (pinfunction "2_2") (pintype "passive"))
      (node (ref "SW15") (pin "1") (pinfunction "1_1") (pintype "passive"))
      (node (ref "SW15") (pin "2") (pinfunction "2_2") (pintype "passive"))
      (node (ref "SW16") (pin "1") (pinfunction "1_1") (pintype "passive"))
      (node (ref "SW16") (pin "2") (pinfunction "2_2") (pintype "passive"))
      (node (ref "SW17") (pin "1") (pinfunction "1_1") (pintype "passive"))
      (node (ref "SW17") (pin "2") (pinfunction "2_2") (pintype "passive"))
      (node (ref "SW18") (pin "1") (pinfunction "1_1") (pintype "passive"))
      (node (ref "SW18") (pin "2") (pinfunction "2_2") (pintype "passive"))
      (node (ref "SW19") (pin "1") (pinfunction "1_1") (pintype "passive"))
      (node (ref "SW19") (pin "2") (pinfunction "2_2") (pintype "passive"))
      (node (ref "SW20") (pin "1") (pinfunction "1_1") (pintype "passive"))
      (node (ref "SW20") (pin "2") (pinfunction "2_2") (pintype "passive"))
      (node (ref "SW21") (pin "1") (pinfunction "1_1") (pintype "passive"))
      (node (ref "SW21") (pin "2") (pinfunction "2_2") (pintype "passive"))
      (node (ref "SW22") (pin "C") (pinfunction "C_C") (pintype "passive"))
      (node (ref "SW22") (pin "GND@1") (pinfunction "GND_GND@1") (pintype "power_in"))
      (node (ref "SW22") (pin "GND@2") (pinfunction "GND_GND@2") (pintype "power_in"))
      (node (ref "SW22") (pin "GND@3") (pinfunction "GND_GND@3") (pintype "power_in"))
      (node (ref "SW22") (pin "GND@4") (pinfunction "GND_GND@4") (pintype "power_in"))
      (node (ref "SW22") (pin "GND@5") (pinfunction "GND_GND@5") (pintype "power_in"))
      (node (ref "SW22") (pin "GND@6") (pinfunction "GND_GND@6") (pintype "power_in"))
      (node (ref "SW22") (pin "GND@7") (pinfunction "GND_GND@7") (pintype "power_in"))
      (node (ref "SW22") (pin "GND@8") (pinfunction "GND_GND@8") (pintype "power_in"))
      (node (ref "SWR/CAL") (pin "1") (pinfunction "E_1") (pintype "passive"))
      (node (ref "SWR/CAL") (pin "4") (pinfunction "P$1_4") (pintype "power_in"))
      (node (ref "SWR/CAL") (pin "5") (pinfunction "P$2_5") (pintype "power_in"))
      (node (ref "T1") (pin "3") (pinfunction "E_3") (pintype "passive"))
      (node (ref "T4") (pin "3") (pinfunction "E_3") (pintype "passive"))
      (node (ref "T5") (pin "C") (pinfunction "C_C") (pintype "passive"))
      (node (ref "T6") (pin "C") (pinfunction "C_C") (pintype "passive"))
      (node (ref "U1") (pin "11") (pinfunction "11_11") (pintype "passive"))
      (node (ref "U1") (pin "12") (pinfunction "12_12") (pintype "passive"))
      (node (ref "U1") (pin "2") (pinfunction "2_2") (pintype "passive"))
      (node (ref "U2") (pin "11") (pinfunction "11_11") (pintype "passive"))
      (node (ref "U2") (pin "12") (pinfunction "12_12") (pintype "passive"))
      (node (ref "U2") (pin "9") (pinfunction "9_9") (pintype "passive"))
      (node (ref "U3") (pin "11") (pinfunction "11_11") (pintype "passive"))
      (node (ref "U3") (pin "12") (pinfunction "12_12") (pintype "passive"))
      (node (ref "U3") (pin "2") (pinfunction "2_2") (pintype "passive"))
      (node (ref "VOLUME") (pin "4") (pinfunction "P$1_4") (pintype "power_in"))
      (node (ref "VOLUME") (pin "5") (pinfunction "P$2_5") (pintype "power_in"))
    )
    (net (code "10") (name "Net-(C1-Pad1)") (class "Default")
      (node (ref "C1") (pin "1") (pinfunction "1_1") (pintype "passive"))
      (node (ref "C2") (pin "2") (pinfunction "2_2") (pintype "passive"))
      (node (ref "R28") (pin "2") (pinfunction "2_2") (pintype "passive"))
    )
    (net (code "11") (name "Net-(C1-Pad2)") (class "Default")
      (node (ref "C1") (pin "2") (pinfunction "2_2") (pintype "passive"))
      (node (ref "U1") (pin "5") (pinfunction "5_5") (pintype "passive"))
    )
    (net (code "12") (name "Net-(C4-Pad-)") (class "Default")
      (node (ref "C4") (pin "-") (pinfunction "-_-") (pintype "passive"))
      (node (ref "R15") (pin "2") (pinfunction "2_2") (pintype "passive"))
      (node (ref "R31") (pin "1") (pinfunction "1_1") (pintype "passive"))
    )
    (net (code "13") (name "Net-(C18-Pad1)") (class "Default")
      (node (ref "C18") (pin "1") (pinfunction "1_1") (pintype "passive"))
      (node (ref "PTT") (pin "MP") (pinfunction "MP_MP") (pintype "passive"))
      (node (ref "R8") (pin "2") (pinfunction "2_2") (pintype "passive"))
    )
    (net (code "14") (name "Net-(C25-Pad2)") (class "Default")
      (node (ref "C25") (pin "2") (pinfunction "2_2") (pintype "passive"))
      (node (ref "D1") (pin "A") (pinfunction "A_A") (pintype "passive"))
      (node (ref "D2") (pin "A") (pinfunction "A_A") (pintype "passive"))
      (node (ref "D3") (pin "A") (pinfunction "A_A") (pintype "passive"))
      (node (ref "U1") (pin "1") (pinfunction "1_1") (pintype "passive"))
    )
    (net (code "15") (name "Net-(C32-Pad2)") (class "Default")
      (node (ref "C32") (pin "2") (pinfunction "2_2") (pintype "passive"))
      (node (ref "R2") (pin "2") (pinfunction "2_2") (pintype "passive"))
      (node (ref "R4") (pin "2") (pinfunction "2_2") (pintype "passive"))
      (node (ref "U2") (pin "5") (pinfunction "5_5") (pintype "passive"))
    )
    (net (code "16") (name "Net-(CLARIFIER-A)") (class "Default")
      (node (ref "CLARIFIER") (pin "3") (pinfunction "A_3") (pintype "passive"))
      (node (ref "R6") (pin "1") (pinfunction "1_1") (pintype "passive"))
    )
    (net (code "17") (name "Net-(CLARIFIER-E)") (class "Default")
      (node (ref "CLARIFIER") (pin "1") (pinfunction "E_1") (pintype "passive"))
      (node (ref "R5") (pin "1") (pinfunction "1_1") (pintype "passive"))
    )
    (net (code "18") (name "Net-(CLARIFIER-S)") (class "Default")
      (node (ref "CLARIFIER") (pin "2") (pinfunction "S_2") (pintype "passive"))
      (node (ref "U2") (pin "7") (pinfunction "7_7") (pintype "passive"))
    )
    (net (code "19") (name "Net-(D4-PadC)") (class "Default")
      (node (ref "D4") (pin "C") (pinfunction "C_C") (pintype "passive"))
      (node (ref "R4") (pin "1") (pinfunction "1_1") (pintype "passive"))
      (node (ref "R5") (pin "2") (pinfunction "2_2") (pintype "passive"))
    )
    (net (code "20") (name "Net-(DISPLAY1-D1_A)") (class "Default")
      (node (ref "C15") (pin "+") (pinfunction "+_+") (pintype "passive"))
      (node (ref "C19") (pin "2") (pinfunction "2_2") (pintype "passive"))
      (node (ref "C33") (pin "+") (pinfunction "+_+") (pintype "passive"))
      (node (ref "C34") (pin "+") (pinfunction "+_+") (pintype "passive"))
      (node (ref "DISPLAY1") (pin "A1") (pinfunction "D1_A_A1") (pintype "input"))
      (node (ref "DISPLAY1") (pin "A2") (pinfunction "D2_A_A2") (pintype "input"))
      (node (ref "DISPLAY1") (pin "A3") (pinfunction "D3_A_A3") (pintype "input"))
      (node (ref "DISPLAY1") (pin "A4") (pinfunction "D4_A_A4") (pintype "input"))
      (node (ref "IC2") (pin "8") (pinfunction "V+_8") (pintype "power_in"))
      (node (ref "LED01") (pin "A") (pinfunction "A_A") (pintype "passive"))
      (node (ref "LED02") (pin "A") (pinfunction "A_A") (pintype "passive"))
      (node (ref "LED03") (pin "A") (pinfunction "A_A") (pintype "passive"))
      (node (ref "LED04") (pin "A") (pinfunction "A_A") (pintype "passive"))
      (node (ref "LED05") (pin "A") (pinfunction "A_A") (pintype "passive"))
      (node (ref "LED06") (pin "A") (pinfunction "A_A") (pintype "passive"))
      (node (ref "LED07") (pin "A") (pinfunction "A_A") (pintype "passive"))
      (node (ref "LED08") (pin "A") (pinfunction "A_A") (pintype "passive"))
      (node (ref "LED09") (pin "A") (pinfunction "A_A") (pintype "passive"))
      (node (ref "LED10") (pin "A") (pinfunction "A_A") (pintype "passive"))
      (node (ref "LED11") (pin "A") (pinfunction "A_A") (pintype "passive"))
      (node (ref "LED12") (pin "A") (pinfunction "A_A") (pintype "passive"))
      (node (ref "LED13") (pin "A") (pinfunction "A_A") (pintype "passive"))
      (node (ref "LED14") (pin "A") (pinfunction "A_A") (pintype "passive"))
      (node (ref "LED15") (pin "A") (pinfunction "A_A") (pintype "passive"))
      (node (ref "LED16") (pin "A") (pinfunction "A_A") (pintype "passive"))
      (node (ref "LED17") (pin "A") (pinfunction "A_A") (pintype "passive"))
      (node (ref "LED18") (pin "A") (pinfunction "A_A") (pintype "passive"))
      (node (ref "LED19") (pin "A") (pinfunction "A_A") (pintype "passive"))
      (node (ref "LED20") (pin "A") (pinfunction "A_A") (pintype "passive"))
      (node (ref "R17") (pin "2") (pinfunction "2_2") (pintype "passive"))
      (node (ref "R18") (pin "2") (pinfunction "2_2") (pintype "passive"))
      (node (ref "U1") (pin "4") (pinfunction "4_4") (pintype "passive"))
    )
    (net (code "21") (name "Net-(DISPLAY1-D1_K)") (class "Default")
      (node (ref "DISPLAY1") (pin "K1") (pinfunction "D1_K_K1") (pintype "input"))
      (node (ref "IC3") (pin "17") (pinfunction "/OUT10_17") (pintype "bidirectional"))
    )
    (net (code "22") (name "Net-(DISPLAY1-D2_K)") (class "Default")
      (node (ref "DISPLAY1") (pin "K2") (pinfunction "D2_K_K2") (pintype "input"))
      (node (ref "IC3") (pin "18") (pinfunction "/OUT11_18") (pintype "bidirectional"))
    )
    (net (code "23") (name "Net-(DISPLAY1-D3_K)") (class "Default")
      (node (ref "DISPLAY1") (pin "K3") (pinfunction "D3_K_K3") (pintype "input"))
      (node (ref "IC4") (pin "17") (pinfunction "/OUT10_17") (pintype "bidirectional"))
    )
    (net (code "24") (name "Net-(DISPLAY1-D4_K)") (class "Default")
      (node (ref "DISPLAY1") (pin "K4") (pinfunction "D4_K_K4") (pintype "input"))
      (node (ref "IC4") (pin "18") (pinfunction "/OUT11_18") (pintype "bidirectional"))
    )
    (net (code "25") (name "Net-(IC1-(A11)PC3)") (class "Default")
      (node (ref "C29") (pin "2") (pinfunction "2_2") (pintype "passive"))
      (node (ref "IC1") (pin "38") (pinfunction "(A11)PC3_38") (pintype "output"))
      (node (ref "PC3") (pin "MP") (pinfunction "MP_MP") (pintype "passive"))
    )
    (net (code "26") (name "Net-(IC1-(A12)PC4)") (class "Default")
      (node (ref "C28") (pin "2") (pinfunction "2_2") (pintype "passive"))
      (node (ref "IC1") (pin "39") (pinfunction "(A12)PC4_39") (pintype "output"))
      (node (ref "PC4") (pin "MP") (pinfunction "MP_MP") (pintype "passive"))
    )
    (net (code "27") (name "Net-(IC1-(AD2)PA2)") (class "Default")
      (node (ref "C26") (pin "2") (pinfunction "2_2") (pintype "passive"))
      (node (ref "IC1") (pin "49") (pinfunction "(AD2)PA2_49") (pintype "bidirectional"))
      (node (ref "R29") (pin "2") (pinfunction "2_2") (pintype "passive"))
      (node (ref "U1") (pin "6") (pinfunction "6_6") (pintype "passive"))
    )
    (net (code "28") (name "Net-(IC1-(AD3)PA3)") (class "Default")
      (node (ref "C11") (pin "2") (pinfunction "2_2") (pintype "passive"))
      (node (ref "IC1") (pin "48") (pinfunction "(AD3)PA3_48") (pintype "bidirectional"))
      (node (ref "U1") (pin "8") (pinfunction "8_8") (pintype "passive"))
    )
    (net (code "29") (name "Net-(IC1-(AD4)PA4)") (class "Default")
      (node (ref "C12") (pin "2") (pinfunction "2_2") (pintype "passive"))
      (node (ref "IC1") (pin "47") (pinfunction "(AD4)PA4_47") (pintype "bidirectional"))
      (node (ref "U1") (pin "10") (pinfunction "10_10") (pintype "passive"))
    )
    (net (code "30") (name "Net-(IC1-(AD5)PA5)") (class "Default")
      (node (ref "C10") (pin "2") (pinfunction "2_2") (pintype "passive"))
      (node (ref "IC1") (pin "46") (pinfunction "(AD5)PA5_46") (pintype "bidirectional"))
      (node (ref "U1") (pin "9") (pinfunction "9_9") (pintype "passive"))
    )
    (net (code "31") (name "Net-(IC1-(AD6)PA6)") (class "Default")
      (node (ref "C9") (pin "2") (pinfunction "2_2") (pintype "passive"))
      (node (ref "IC1") (pin "45") (pinfunction "(AD6)PA6_45") (pintype "bidirectional"))
      (node (ref "U1") (pin "7") (pinfunction "7_7") (pintype "passive"))
    )
    (net (code "32") (name "Net-(IC1-(AD7)PA7)") (class "Default")
      (node (ref "IC1") (pin "44") (pinfunction "(AD7)PA7_44") (pintype "bidirectional"))
      (node (ref "R12") (pin "1") (pinfunction "1_1") (pintype "passive"))
    )
    (net (code "33") (name "Net-(IC1-(IC3{slash}INT7)PE7)") (class "Default")
      (node (ref "C3") (pin "+") (pinfunction "+_+") (pintype "passive"))
      (node (ref "IC1") (pin "9") (pinfunction "(IC3/INT7)PE7_9") (pintype "bidirectional"))
      (node (ref "R25") (pin "1") (pinfunction "1_1") (pintype "passive"))
    )
    (net (code "34") (name "Net-(IC1-(MISO)PB3)") (class "Default")
      (node (ref "IC1") (pin "13") (pinfunction "(MISO)PB3_13") (pintype "bidirectional"))
      (node (ref "IC7") (pin "2") (pinfunction "SO_2") (pintype "bidirectional"))
    )
    (net (code "35") (name "Net-(IC1-(MOSI)PB2)") (class "Default")
      (node (ref "IC1") (pin "12") (pinfunction "(MOSI)PB2_12") (pintype "bidirectional"))
      (node (ref "IC7") (pin "5") (pinfunction "SI_5") (pintype "input"))
    )
    (net (code "36") (name "Net-(IC1-(OC1A)PB5)") (class "Default")
      (node (ref "IC1") (pin "15") (pinfunction "(OC1A)PB5_15") (pintype "bidirectional"))
      (node (ref "IC9") (pin "5") (pinfunction "RW_5") (pintype "bidirectional"))
    )
    (net (code "37") (name "Net-(IC1-(OC3A{slash}AIN1)PE3)") (class "Default")
      (node (ref "IC1") (pin "5") (pinfunction "(OC3A/AIN1)PE3_5") (pintype "bidirectional"))
      (node (ref "SPK") (pin "MP") (pinfunction "MP_MP") (pintype "passive"))
    )
    (net (code "38") (name "Net-(IC1-(OC3B{slash}INT4)PE4)") (class "Default")
      (node (ref "C31") (pin "1") (pinfunction "1_1") (pintype "passive"))
      (node (ref "D3") (pin "C") (pinfunction "C_C") (pintype "passive"))
      (node (ref "IC1") (pin "6") (pinfunction "(OC3B/INT4)PE4_6") (pintype "bidirectional"))
      (node (ref "R23") (pin "2") (pinfunction "2_2") (pintype "passive"))
    )
    (net (code "39") (name "Net-(IC1-(OC3C{slash}INT5)PE5)") (class "Default")
      (node (ref "IC1") (pin "7") (pinfunction "(OC3C/INT5)PE5_7") (pintype "bidirectional"))
      (node (ref "SW01") (pin "3") (pinfunction "3_3") (pintype "passive"))
      (node (ref "SW01") (pin "4") (pinfunction "4_4") (pintype "passive"))
    )
    (net (code "40") (name "Net-(IC1-(SS)PB0)") (class "Default")
      (node (ref "IC1") (pin "10") (pinfunction "(SS)PB0_10") (pintype "bidirectional"))
      (node (ref "IC7") (pin "1") (pinfunction "~{CS}_1") (pintype "input"))
    )
    (net (code "41") (name "Net-(IC1-(T3{slash}INT6)PE6)") (class "Default")
      (node (ref "C30") (pin "1") (pinfunction "1_1") (pintype "passive"))
      (node (ref "IC1") (pin "8") (pinfunction "(T3/INT6)PE6_8") (pintype "bidirectional"))
      (node (ref "PE6") (pin "MP") (pinfunction "MP_MP") (pintype "passive"))
    )
    (net (code "42") (name "Net-(IC1-AVCC)") (class "Default")
      (node (ref "C7") (pin "2") (pinfunction "2_2") (pintype "passive"))
      (node (ref "IC1") (pin "64") (pinfunction "AVCC_64") (pintype "power_in"))
      (node (ref "L1") (pin "1") (pinfunction "1_1") (pintype "passive"))
    )
    (net (code "43") (name "Net-(IC1-PF1(ADC1))") (class "Default")
      (node (ref "IC1") (pin "60") (pinfunction "PF1(ADC1)_60") (pintype "input"))
      (node (ref "SWR/CAL") (pin "3") (pinfunction "A_3") (pintype "passive"))
      (node (ref "U2") (pin "10") (pinfunction "10_10") (pintype "passive"))
    )
    (net (code "44") (name "Net-(IC1-XTAL1)") (class "Default")
      (node (ref "C6") (pin "2") (pinfunction "2_2") (pintype "passive"))
      (node (ref "IC1") (pin "24") (pinfunction "XTAL1_24") (pintype "bidirectional"))
      (node (ref "Q1") (pin "2") (pinfunction "2_2") (pintype "passive"))
    )
    (net (code "45") (name "Net-(IC1-XTAL2)") (class "Default")
      (node (ref "C5") (pin "2") (pinfunction "2_2") (pintype "passive"))
      (node (ref "IC1") (pin "23") (pinfunction "XTAL2_23") (pintype "bidirectional"))
      (node (ref "Q1") (pin "1") (pinfunction "1_1") (pintype "passive"))
    )
    (net (code "46") (name "Net-(IC2A-+IN)") (class "Default")
      (node (ref "C20") (pin "2") (pinfunction "2_2") (pintype "passive"))
      (node (ref "IC2") (pin "3") (pinfunction "+IN_3") (pintype "input"))
      (node (ref "IC2") (pin "6") (pinfunction "-IN_6") (pintype "input"))
      (node (ref "R10") (pin "2") (pinfunction "2_2") (pintype "passive"))
      (node (ref "R17") (pin "1") (pinfunction "1_1") (pintype "passive"))
      (node (ref "UP/DOWN") (pin "MP") (pinfunction "MP_MP") (pintype "passive"))
    )
    (net (code "47") (name "Net-(IC2A--IN)") (class "Default")
      (node (ref "IC2") (pin "2") (pinfunction "-IN_2") (pintype "input"))
      (node (ref "R18") (pin "1") (pinfunction "1_1") (pintype "passive"))
      (node (ref "R19") (pin "2") (pinfunction "2_2") (pintype "passive"))
    )
    (net (code "48") (name "Net-(IC2A-OUT)") (class "Default")
      (node (ref "IC2") (pin "1") (pinfunction "OUT_1") (pintype "output"))
      (node (ref "R11") (pin "2") (pinfunction "2_2") (pintype "passive"))
      (node (ref "R21") (pin "2") (pinfunction "2_2") (pintype "passive"))
    )
    (net (code "49") (name "Net-(IC2B-+IN)") (class "Default")
      (node (ref "IC2") (pin "5") (pinfunction "+IN_5") (pintype "input"))
      (node (ref "R19") (pin "1") (pinfunction "1_1") (pintype "passive"))
      (node (ref "R20") (pin "2") (pinfunction "2_2") (pintype "passive"))
    )
    (net (code "50") (name "Net-(IC2B-OUT)") (class "Default")
      (node (ref "IC2") (pin "7") (pinfunction "OUT_7") (pintype "output"))
      (node (ref "R1") (pin "2") (pinfunction "2_2") (pintype "passive"))
      (node (ref "R22") (pin "2") (pinfunction "2_2") (pintype "passive"))
    )
    (net (code "51") (name "Net-(IC3-REXT)") (class "Default")
      (node (ref "IC3") (pin "1") (pinfunction "REXT_1") (pintype "bidirectional"))
      (node (ref "R3") (pin "2") (pinfunction "2_2") (pintype "passive"))
    )
    (net (code "52") (name "Net-(IC3-{slash}OUT0)") (class "Default")
      (node (ref "IC3") (pin "6") (pinfunction "/OUT0_6") (pintype "bidirectional"))
      (node (ref "LED07") (pin "C") (pinfunction "C_C") (pintype "passive"))
    )
    (net (code "53") (name "Net-(IC3-{slash}OUT1)") (class "Default")
      (node (ref "IC3") (pin "7") (pinfunction "/OUT1_7") (pintype "bidirectional"))
      (node (ref "LED08") (pin "C") (pinfunction "C_C") (pintype "passive"))
    )
    (net (code "54") (name "Net-(IC3-{slash}OUT2)") (class "Default")
      (node (ref "IC3") (pin "8") (pinfunction "/OUT2_8") (pintype "bidirectional"))
      (node (ref "LED05") (pin "C") (pinfunction "C_C") (pintype "passive"))
    )
    (net (code "55") (name "Net-(IC3-{slash}OUT3)") (class "Default")
      (node (ref "IC3") (pin "9") (pinfunction "/OUT3_9") (pintype "bidirectional"))
      (node (ref "LED06") (pin "C") (pinfunction "C_C") (pintype "passive"))
    )
    (net (code "56") (name "Net-(IC3-{slash}OUT4)") (class "Default")
      (node (ref "IC3") (pin "11") (pinfunction "/OUT4_11") (pintype "bidirectional"))
      (node (ref "LED03") (pin "C") (pinfunction "C_C") (pintype "passive"))
    )
    (net (code "57") (name "Net-(IC3-{slash}OUT5)") (class "Default")
      (node (ref "IC3") (pin "12") (pinfunction "/OUT5_12") (pintype "bidirectional"))
      (node (ref "LED04") (pin "C") (pinfunction "C_C") (pintype "passive"))
    )
    (net (code "58") (name "Net-(IC3-{slash}OUT6)") (class "Default")
      (node (ref "IC3") (pin "13") (pinfunction "/OUT6_13") (pintype "bidirectional"))
      (node (ref "LED01") (pin "C") (pinfunction "C_C") (pintype "passive"))
    )
    (net (code "59") (name "Net-(IC3-{slash}OUT7)") (class "Default")
      (node (ref "IC3") (pin "14") (pinfunction "/OUT7_14") (pintype "bidirectional"))
      (node (ref "LED02") (pin "C") (pinfunction "C_C") (pintype "passive"))
    )
    (net (code "60") (name "Net-(IC3-{slash}OUT8)") (class "Default")
      (node (ref "IC3") (pin "15") (pinfunction "/OUT8_15") (pintype "bidirectional"))
      (node (ref "LED09") (pin "C") (pinfunction "C_C") (pintype "passive"))
    )
    (net (code "61") (name "Net-(IC3-{slash}OUT9)") (class "Default")
      (node (ref "IC3") (pin "16") (pinfunction "/OUT9_16") (pintype "bidirectional"))
      (node (ref "LED10") (pin "C") (pinfunction "C_C") (pintype "passive"))
    )
    (net (code "62") (name "Net-(IC3-{slash}RESET)") (class "Default")
      (node (ref "IC3") (pin "25") (pinfunction "/RESET_25") (pintype "bidirectional"))
      (node (ref "R13") (pin "2") (pinfunction "2_2") (pintype "passive"))
    )
    (net (code "63") (name "Net-(IC4-REXT)") (class "Default")
      (node (ref "IC4") (pin "1") (pinfunction "REXT_1") (pintype "bidirectional"))
      (node (ref "R16") (pin "2") (pinfunction "2_2") (pintype "passive"))
    )
    (net (code "64") (name "Net-(IC4-{slash}OUT0)") (class "Default")
      (node (ref "IC4") (pin "6") (pinfunction "/OUT0_6") (pintype "bidirectional"))
      (node (ref "LED17") (pin "C") (pinfunction "C_C") (pintype "passive"))
    )
    (net (code "65") (name "Net-(IC4-{slash}OUT1)") (class "Default")
      (node (ref "IC4") (pin "7") (pinfunction "/OUT1_7") (pintype "bidirectional"))
      (node (ref "LED18") (pin "C") (pinfunction "C_C") (pintype "passive"))
    )
    (net (code "66") (name "Net-(IC4-{slash}OUT2)") (class "Default")
      (node (ref "IC4") (pin "8") (pinfunction "/OUT2_8") (pintype "bidirectional"))
      (node (ref "LED15") (pin "C") (pinfunction "C_C") (pintype "passive"))
    )
    (net (code "67") (name "Net-(IC4-{slash}OUT3)") (class "Default")
      (node (ref "IC4") (pin "9") (pinfunction "/OUT3_9") (pintype "bidirectional"))
      (node (ref "LED16") (pin "C") (pinfunction "C_C") (pintype "passive"))
    )
    (net (code "68") (name "Net-(IC4-{slash}OUT4)") (class "Default")
      (node (ref "IC4") (pin "11") (pinfunction "/OUT4_11") (pintype "bidirectional"))
      (node (ref "LED11") (pin "C") (pinfunction "C_C") (pintype "passive"))
    )
    (net (code "69") (name "Net-(IC4-{slash}OUT5)") (class "Default")
      (node (ref "IC4") (pin "12") (pinfunction "/OUT5_12") (pintype "bidirectional"))
      (node (ref "LED12") (pin "C") (pinfunction "C_C") (pintype "passive"))
    )
    (net (code "70") (name "Net-(IC4-{slash}OUT6)") (class "Default")
      (node (ref "IC4") (pin "13") (pinfunction "/OUT6_13") (pintype "bidirectional"))
      (node (ref "LED13") (pin "C") (pinfunction "C_C") (pintype "passive"))
    )
    (net (code "71") (name "Net-(IC4-{slash}OUT7)") (class "Default")
      (node (ref "IC4") (pin "14") (pinfunction "/OUT7_14") (pintype "bidirectional"))
      (node (ref "LED14") (pin "C") (pinfunction "C_C") (pintype "passive"))
    )
    (net (code "72") (name "Net-(IC4-{slash}OUT8)") (class "Default")
      (node (ref "IC4") (pin "15") (pinfunction "/OUT8_15") (pintype "bidirectional"))
      (node (ref "LED19") (pin "C") (pinfunction "C_C") (pintype "passive"))
    )
    (net (code "73") (name "Net-(IC4-{slash}OUT9)") (class "Default")
      (node (ref "IC4") (pin "16") (pinfunction "/OUT9_16") (pintype "bidirectional"))
      (node (ref "LED20") (pin "C") (pinfunction "C_C") (pintype "passive"))
    )
    (net (code "74") (name "Net-(IC4-{slash}RESET)") (class "Default")
      (node (ref "IC4") (pin "25") (pinfunction "/RESET_25") (pintype "bidirectional"))
      (node (ref "R33") (pin "2") (pinfunction "2_2") (pintype "passive"))
    )
    (net (code "75") (name "Net-(IC5-I{slash}O0.0)") (class "Default")
      (node (ref "IC5") (pin "4") (pinfunction "I/O0.0_4") (pintype "bidirectional"))
      (node (ref "SW13") (pin "3") (pinfunction "3_3") (pintype "passive"))
      (node (ref "SW13") (pin "4") (pinfunction "4_4") (pintype "passive"))
    )
    (net (code "76") (name "Net-(IC5-I{slash}O0.1)") (class "Default")
      (node (ref "IC5") (pin "5") (pinfunction "I/O0.1_5") (pintype "bidirectional"))
      (node (ref "SW14") (pin "3") (pinfunction "3_3") (pintype "passive"))
      (node (ref "SW14") (pin "4") (pinfunction "4_4") (pintype "passive"))
    )
    (net (code "77") (name "Net-(IC5-I{slash}O0.2)") (class "Default")
      (node (ref "IC5") (pin "6") (pinfunction "I/O0.2_6") (pintype "bidirectional"))
      (node (ref "SW15") (pin "3") (pinfunction "3_3") (pintype "passive"))
      (node (ref "SW15") (pin "4") (pinfunction "4_4") (pintype "passive"))
    )
    (net (code "78") (name "Net-(IC5-I{slash}O0.6)") (class "Default")
      (node (ref "IC5") (pin "10") (pinfunction "I/O0.6_10") (pintype "bidirectional"))
      (node (ref "T5") (pin "E") (pinfunction "E_E") (pintype "passive"))
    )
    (net (code "79") (name "Net-(IC5-I{slash}O0.7)") (class "Default")
      (node (ref "IC5") (pin "11") (pinfunction "I/O0.7_11") (pintype "bidirectional"))
      (node (ref "T6") (pin "E") (pinfunction "E_E") (pintype "passive"))
    )
    (net (code "80") (name "Net-(IC5-I{slash}O1.0)") (class "Default")
      (node (ref "IC5") (pin "13") (pinfunction "I/O1.0_13") (pintype "bidirectional"))
      (node (ref "SW17") (pin "3") (pinfunction "3_3") (pintype "passive"))
      (node (ref "SW17") (pin "4") (pinfunction "4_4") (pintype "passive"))
    )
    (net (code "81") (name "Net-(IC5-I{slash}O1.1)") (class "Default")
      (node (ref "C21") (pin "2") (pinfunction "2_2") (pintype "passive"))
      (node (ref "IC5") (pin "14") (pinfunction "I/O1.1_14") (pintype "bidirectional"))
      (node (ref "SW22") (pin "B") (pinfunction "B_B") (pintype "passive"))
    )
    (net (code "82") (name "Net-(IC5-I{slash}O1.2)") (class "Default")
      (node (ref "C22") (pin "2") (pinfunction "2_2") (pintype "passive"))
      (node (ref "IC5") (pin "15") (pinfunction "I/O1.2_15") (pintype "bidirectional"))
      (node (ref "SW22") (pin "A") (pinfunction "A_A") (pintype "passive"))
    )
    (net (code "83") (name "Net-(IC5-I{slash}O1.3)") (class "Default")
      (node (ref "IC5") (pin "16") (pinfunction "I/O1.3_16") (pintype "bidirectional"))
      (node (ref "SW16") (pin "3") (pinfunction "3_3") (pintype "passive"))
      (node (ref "SW16") (pin "4") (pinfunction "4_4") (pintype "passive"))
    )
    (net (code "84") (name "Net-(IC5-I{slash}O1.4)") (class "Default")
      (node (ref "IC5") (pin "17") (pinfunction "I/O1.4_17") (pintype "bidirectional"))
      (node (ref "SW19") (pin "3") (pinfunction "3_3") (pintype "passive"))
      (node (ref "SW19") (pin "4") (pinfunction "4_4") (pintype "passive"))
    )
    (net (code "85") (name "Net-(IC5-I{slash}O1.5)") (class "Default")
      (node (ref "IC5") (pin "18") (pinfunction "I/O1.5_18") (pintype "bidirectional"))
      (node (ref "SW18") (pin "3") (pinfunction "3_3") (pintype "passive"))
      (node (ref "SW18") (pin "4") (pinfunction "4_4") (pintype "passive"))
    )
    (net (code "86") (name "Net-(IC5-I{slash}O1.6)") (class "Default")
      (node (ref "IC5") (pin "19") (pinfunction "I/O1.6_19") (pintype "bidirectional"))
      (node (ref "SW21") (pin "3") (pinfunction "3_3") (pintype "passive"))
      (node (ref "SW21") (pin "4") (pinfunction "4_4") (pintype "passive"))
    )
    (net (code "87") (name "Net-(IC5-I{slash}O1.7)") (class "Default")
      (node (ref "IC5") (pin "20") (pinfunction "I/O1.7_20") (pintype "bidirectional"))
      (node (ref "SW20") (pin "3") (pinfunction "3_3") (pintype "passive"))
      (node (ref "SW20") (pin "4") (pinfunction "4_4") (pintype "passive"))
    )
    (net (code "88") (name "Net-(IC5-~{INT})") (class "Default")
      (node (ref "IC5") (pin "1") (pinfunction "~{INT}_1") (pintype "output"))
      (node (ref "IC6") (pin "1") (pinfunction "~{INT}_1") (pintype "output"))
      (node (ref "R25") (pin "2") (pinfunction "2_2") (pintype "passive"))
    )
    (net (code "89") (name "Net-(IC6-I{slash}O0.0)") (class "Default")
      (node (ref "IC6") (pin "4") (pinfunction "I/O0.0_4") (pintype "bidirectional"))
      (node (ref "SW12") (pin "3") (pinfunction "3_3") (pintype "passive"))
      (node (ref "SW12") (pin "4") (pinfunction "4_4") (pintype "passive"))
    )
    (net (code "90") (name "Net-(IC6-I{slash}O0.1)") (class "Default")
      (node (ref "IC6") (pin "5") (pinfunction "I/O0.1_5") (pintype "bidirectional"))
      (node (ref "SW11") (pin "3") (pinfunction "3_3") (pintype "passive"))
      (node (ref "SW11") (pin "4") (pinfunction "4_4") (pintype "passive"))
    )
    (net (code "91") (name "Net-(IC6-I{slash}O0.2)") (class "Default")
      (node (ref "IC6") (pin "6") (pinfunction "I/O0.2_6") (pintype "bidirectional"))
      (node (ref "SW10") (pin "3") (pinfunction "3_3") (pintype "passive"))
      (node (ref "SW10") (pin "4") (pinfunction "4_4") (pintype "passive"))
    )
    (net (code "92") (name "Net-(IC6-I{slash}O0.3)") (class "Default")
      (node (ref "IC6") (pin "7") (pinfunction "I/O0.3_7") (pintype "bidirectional"))
      (node (ref "SW02") (pin "3") (pinfunction "3_3") (pintype "passive"))
      (node (ref "SW02") (pin "4") (pinfunction "4_4") (pintype "passive"))
    )
    (net (code "93") (name "Net-(IC6-I{slash}O0.4)") (class "Default")
      (node (ref "IC6") (pin "8") (pinfunction "I/O0.4_8") (pintype "bidirectional"))
      (node (ref "SW03") (pin "3") (pinfunction "3_3") (pintype "passive"))
      (node (ref "SW03") (pin "4") (pinfunction "4_4") (pintype "passive"))
    )
    (net (code "94") (name "Net-(IC6-I{slash}O0.5)") (class "Default")
      (node (ref "IC6") (pin "9") (pinfunction "I/O0.5_9") (pintype "bidirectional"))
      (node (ref "SW04") (pin "3") (pinfunction "3_3") (pintype "passive"))
      (node (ref "SW04") (pin "4") (pinfunction "4_4") (pintype "passive"))
    )
    (net (code "95") (name "Net-(IC6-I{slash}O0.6)") (class "Default")
      (node (ref "IC6") (pin "10") (pinfunction "I/O0.6_10") (pintype "bidirectional"))
      (node (ref "SW05") (pin "3") (pinfunction "3_3") (pintype "passive"))
      (node (ref "SW05") (pin "4") (pinfunction "4_4") (pintype "passive"))
    )
    (net (code "96") (name "Net-(IC6-I{slash}O1.0)") (class "Default")
      (node (ref "IC6") (pin "13") (pinfunction "I/O1.0_13") (pintype "bidirectional"))
      (node (ref "SW06") (pin "3") (pinfunction "3_3") (pintype "passive"))
      (node (ref "SW06") (pin "4") (pinfunction "4_4") (pintype "passive"))
    )
    (net (code "97") (name "Net-(IC6-I{slash}O1.1)") (class "Default")
      (node (ref "IC6") (pin "14") (pinfunction "I/O1.1_14") (pintype "bidirectional"))
      (node (ref "R8") (pin "1") (pinfunction "1_1") (pintype "passive"))
      (node (ref "R9") (pin "2") (pinfunction "2_2") (pintype "passive"))
    )
    (net (code "98") (name "Net-(IC6-I{slash}O1.2)") (class "Default")
      (node (ref "IC6") (pin "15") (pinfunction "I/O1.2_15") (pintype "bidirectional"))
      (node (ref "SW07") (pin "3") (pinfunction "3_3") (pintype "passive"))
      (node (ref "SW07") (pin "4") (pinfunction "4_4") (pintype "passive"))
    )
    (net (code "99") (name "Net-(IC6-I{slash}O1.3)") (class "Default")
      (node (ref "IC6") (pin "16") (pinfunction "I/O1.3_16") (pintype "bidirectional"))
      (node (ref "SW08") (pin "3") (pinfunction "3_3") (pintype "passive"))
      (node (ref "SW08") (pin "4") (pinfunction "4_4") (pintype "passive"))
    )
    (net (code "100") (name "Net-(IC6-I{slash}O1.4)") (class "Default")
      (node (ref "IC6") (pin "17") (pinfunction "I/O1.4_17") (pintype "bidirectional"))
      (node (ref "SW09") (pin "3") (pinfunction "3_3") (pintype "passive"))
      (node (ref "SW09") (pin "4") (pinfunction "4_4") (pintype "passive"))
    )
    (net (code "101") (name "Net-(IC8-BP0)") (class "Default")
      (node (ref "DISPLAY1") (pin "COM1") (pinfunction "COM1_COM1") (pintype "input"))
      (node (ref "IC8") (pin "25") (pinfunction "BP0_25") (pintype "output"))
    )
    (net (code "102") (name "Net-(IC8-BP1)") (class "Default")
      (node (ref "DISPLAY1") (pin "COM2") (pinfunction "COM2_COM2") (pintype "input"))
      (node (ref "IC8") (pin "26") (pinfunction "BP1_26") (pintype "output"))
    )
    (net (code "103") (name "Net-(IC8-BP2)") (class "Default")
      (node (ref "DISPLAY1") (pin "COM3") (pinfunction "COM3_COM3") (pintype "input"))
      (node (ref "IC8") (pin "27") (pinfunction "BP2_27") (pintype "output"))
    )
    (net (code "104") (name "Net-(IC8-S0)") (class "Default")
      (node (ref "DISPLAY1") (pin "SEG01") (pinfunction "SEG01_SEG01") (pintype "input"))
      (node (ref "IC8") (pin "29") (pinfunction "S0_29") (pintype "output"))
    )
    (net (code "105") (name "Net-(IC8-S1)") (class "Default")
      (node (ref "DISPLAY1") (pin "SEG02") (pinfunction "SEG02_SEG02") (pintype "input"))
      (node (ref "IC8") (pin "30") (pinfunction "S1_30") (pintype "output"))
    )
    (net (code "106") (name "Net-(IC8-S2)") (class "Default")
      (node (ref "DISPLAY1") (pin "SEG03") (pinfunction "SEG03_SEG03") (pintype "input"))
      (node (ref "IC8") (pin "31") (pinfunction "S2_31") (pintype "output"))
    )
    (net (code "107") (name "Net-(IC8-S3)") (class "Default")
      (node (ref "DISPLAY1") (pin "SEG04") (pinfunction "SEG04_SEG04") (pintype "input"))
      (node (ref "IC8") (pin "32") (pinfunction "S3_32") (pintype "output"))
    )
    (net (code "108") (name "Net-(IC8-S4)") (class "Default")
      (node (ref "DISPLAY1") (pin "SEG05") (pinfunction "SEG05_SEG05") (pintype "input"))
      (node (ref "IC8") (pin "34") (pinfunction "S4_34") (pintype "output"))
    )
    (net (code "109") (name "Net-(IC8-S5)") (class "Default")
      (node (ref "DISPLAY1") (pin "SEG06") (pinfunction "SEG06_SEG06") (pintype "input"))
      (node (ref "IC8") (pin "35") (pinfunction "S5_35") (pintype "output"))
    )
    (net (code "110") (name "Net-(IC8-S6)") (class "Default")
      (node (ref "DISPLAY1") (pin "SEG07") (pinfunction "SEG07_SEG07") (pintype "input"))
      (node (ref "IC8") (pin "36") (pinfunction "S6_36") (pintype "output"))
    )
    (net (code "111") (name "Net-(IC8-S7)") (class "Default")
      (node (ref "DISPLAY1") (pin "SEG08") (pinfunction "SEG08_SEG08") (pintype "input"))
      (node (ref "IC8") (pin "37") (pinfunction "S7_37") (pintype "output"))
    )
    (net (code "112") (name "Net-(IC8-S8)") (class "Default")
      (node (ref "DISPLAY1") (pin "SEG09") (pinfunction "SEG09_SEG09") (pintype "input"))
      (node (ref "IC8") (pin "38") (pinfunction "S8_38") (pintype "output"))
    )
    (net (code "113") (name "Net-(IC8-S9)") (class "Default")
      (node (ref "DISPLAY1") (pin "SEG10") (pinfunction "SEG10_SEG10") (pintype "input"))
      (node (ref "IC8") (pin "39") (pinfunction "S9_39") (pintype "output"))
    )
    (net (code "114") (name "Net-(IC8-S10)") (class "Default")
      (node (ref "DISPLAY1") (pin "SEG11") (pinfunction "SEG11_SEG11") (pintype "input"))
      (node (ref "IC8") (pin "40") (pinfunction "S10_40") (pintype "output"))
    )
    (net (code "115") (name "Net-(IC8-S11)") (class "Default")
      (node (ref "DISPLAY1") (pin "SEG12") (pinfunction "SEG12_SEG12") (pintype "input"))
      (node (ref "IC8") (pin "41") (pinfunction "S11_41") (pintype "output"))
    )
    (net (code "116") (name "Net-(IC8-S12)") (class "Default")
      (node (ref "DISPLAY1") (pin "SEG13") (pinfunction "SEG13_SEG13") (pintype "input"))
      (node (ref "IC8") (pin "42") (pinfunction "S12_42") (pintype "output"))
    )
    (net (code "117") (name "Net-(IC8-S13)") (class "Default")
      (node (ref "DISPLAY1") (pin "SEG14") (pinfunction "SEG14_SEG14") (pintype "input"))
      (node (ref "IC8") (pin "43") (pinfunction "S13_43") (pintype "output"))
    )
    (net (code "118") (name "Net-(IC8-S14)") (class "Default")
      (node (ref "DISPLAY1") (pin "SEG15") (pinfunction "SEG15_SEG15") (pintype "input"))
      (node (ref "IC8") (pin "44") (pinfunction "S14_44") (pintype "output"))
    )
    (net (code "119") (name "Net-(IC8-S15)") (class "Default")
      (node (ref "DISPLAY1") (pin "SEG16") (pinfunction "SEG16_SEG16") (pintype "input"))
      (node (ref "IC8") (pin "45") (pinfunction "S15_45") (pintype "output"))
    )
    (net (code "120") (name "Net-(IC8-S16)") (class "Default")
      (node (ref "DISPLAY1") (pin "SEG17") (pinfunction "SEG17_SEG17") (pintype "input"))
      (node (ref "IC8") (pin "46") (pinfunction "S16_46") (pintype "output"))
    )
    (net (code "121") (name "Net-(IC8-S17)") (class "Default")
      (node (ref "DISPLAY1") (pin "SEG18") (pinfunction "SEG18_SEG18") (pintype "input"))
      (node (ref "IC8") (pin "47") (pinfunction "S17_47") (pintype "output"))
    )
    (net (code "122") (name "Net-(IC8-S18)") (class "Default")
      (node (ref "DISPLAY1") (pin "SEG19") (pinfunction "SEG19_SEG19") (pintype "input"))
      (node (ref "IC8") (pin "49") (pinfunction "S18_49") (pintype "output"))
    )
    (net (code "123") (name "Net-(IC8-S19)") (class "Default")
      (node (ref "DISPLAY1") (pin "SEG20") (pinfunction "SEG20_SEG20") (pintype "input"))
      (node (ref "IC8") (pin "50") (pinfunction "S19_50") (pintype "output"))
    )
    (net (code "124") (name "Net-(IC8-S20)") (class "Default")
      (node (ref "DISPLAY1") (pin "SEG21") (pinfunction "SEG21_SEG21") (pintype "input"))
      (node (ref "IC8") (pin "51") (pinfunction "S20_51") (pintype "output"))
    )
    (net (code "125") (name "Net-(IC8-S21)") (class "Default")
      (node (ref "DISPLAY1") (pin "SEG22") (pinfunction "SEG22_SEG22") (pintype "input"))
      (node (ref "IC8") (pin "52") (pinfunction "S21_52") (pintype "output"))
    )
    (net (code "126") (name "Net-(IC8-S22)") (class "Default")
      (node (ref "DISPLAY1") (pin "SEG23") (pinfunction "SEG23_SEG23") (pintype "input"))
      (node (ref "IC8") (pin "53") (pinfunction "S22_53") (pintype "output"))
    )
    (net (code "127") (name "Net-(IC8-S23)") (class "Default")
      (node (ref "DISPLAY1") (pin "SEG24") (pinfunction "SEG24_SEG24") (pintype "input"))
      (node (ref "IC8") (pin "54") (pinfunction "S23_54") (pintype "output"))
    )
    (net (code "128") (name "Net-(IC8-S24)") (class "Default")
      (node (ref "DISPLAY1") (pin "SEG25") (pinfunction "SEG25_SEG25") (pintype "input"))
      (node (ref "IC8") (pin "55") (pinfunction "S24_55") (pintype "output"))
    )
    (net (code "129") (name "Net-(IC8-S25)") (class "Default")
      (node (ref "DISPLAY1") (pin "SEG26") (pinfunction "SEG26_SEG26") (pintype "input"))
      (node (ref "IC8") (pin "56") (pinfunction "S25_56") (pintype "output"))
    )
    (net (code "130") (name "Net-(IC8-S26)") (class "Default")
      (node (ref "DISPLAY1") (pin "SEG27") (pinfunction "SEG27_SEG27") (pintype "input"))
      (node (ref "IC8") (pin "57") (pinfunction "S26_57") (pintype "output"))
    )
    (net (code "131") (name "Net-(IC8-S27)") (class "Default")
      (node (ref "DISPLAY1") (pin "SEG28") (pinfunction "SEG28_SEG28") (pintype "input"))
      (node (ref "IC8") (pin "58") (pinfunction "S27_58") (pintype "output"))
    )
    (net (code "132") (name "Net-(IC8-S28)") (class "Default")
      (node (ref "DISPLAY1") (pin "SEG29") (pinfunction "SEG29_SEG29") (pintype "input"))
      (node (ref "IC8") (pin "59") (pinfunction "S28_59") (pintype "output"))
    )
    (net (code "133") (name "Net-(IC8-S29)") (class "Default")
      (node (ref "DISPLAY1") (pin "SEG30") (pinfunction "SEG30_SEG30") (pintype "input"))
      (node (ref "IC8") (pin "60") (pinfunction "S29_60") (pintype "output"))
    )
    (net (code "134") (name "Net-(IC8-S30)") (class "Default")
      (node (ref "DISPLAY1") (pin "SEG31") (pinfunction "SEG31_SEG31") (pintype "input"))
      (node (ref "IC8") (pin "61") (pinfunction "S30_61") (pintype "output"))
    )
    (net (code "135") (name "Net-(IC8-S31)") (class "Default")
      (node (ref "DISPLAY1") (pin "SEG32") (pinfunction "SEG32_SEG32") (pintype "input"))
      (node (ref "IC8") (pin "62") (pinfunction "S31_62") (pintype "output"))
    )
    (net (code "136") (name "Net-(IC8-S32)") (class "Default")
      (node (ref "DISPLAY1") (pin "SEG33") (pinfunction "SEG33_SEG33") (pintype "input"))
      (node (ref "IC8") (pin "63") (pinfunction "S32_63") (pintype "output"))
    )
    (net (code "137") (name "Net-(IC8-VLCD)") (class "Default")
      (node (ref "IC8") (pin "21") (pinfunction "VLCD_21") (pintype "power_in"))
      (node (ref "R30") (pin "2") (pinfunction "2_2") (pintype "passive"))
    )
    (net (code "138") (name "Net-(IC9-RH)") (class "Default")
      (node (ref "IC9") (pin "7") (pinfunction "RH_7") (pintype "bidirectional"))
      (node (ref "R28") (pin "1") (pinfunction "1_1") (pintype "passive"))
    )
    (net (code "139") (name "Net-(R1-Pad1)") (class "Default")
      (node (ref "R1") (pin "1") (pinfunction "1_1") (pintype "passive"))
      (node (ref "T6") (pin "B") (pinfunction "B_B") (pintype "passive"))
    )
    (net (code "140") (name "Net-(R7-Pad2)") (class "Default")
      (node (ref "R7") (pin "2") (pinfunction "2_2") (pintype "passive"))
      (node (ref "U2") (pin "8") (pinfunction "8_8") (pintype "passive"))
    )
    (net (code "141") (name "Net-(R11-Pad1)") (class "Default")
      (node (ref "R11") (pin "1") (pinfunction "1_1") (pintype "passive"))
      (node (ref "T5") (pin "B") (pinfunction "B_B") (pintype "passive"))
    )
    (net (code "142") (name "Net-(RF-POWER-S)") (class "Default")
      (node (ref "RF-POWER") (pin "2") (pinfunction "S_2") (pintype "passive"))
      (node (ref "U2") (pin "6") (pinfunction "6_6") (pintype "passive"))
    )
    (net (code "143") (name "Net-(SQUELCH-A)") (class "Default")
      (node (ref "R2") (pin "1") (pinfunction "1_1") (pintype "passive"))
      (node (ref "SQUELCH") (pin "3") (pinfunction "A_3") (pintype "passive"))
    )
    (net (code "144") (name "Net-(SQUELCH-S)") (class "Default")
      (node (ref "SQUELCH") (pin "2") (pinfunction "S_2") (pintype "passive"))
      (node (ref "U2") (pin "4") (pinfunction "4_4") (pintype "passive"))
    )
    (net (code "145") (name "Net-(SWR/CAL-S)") (class "Default")
      (node (ref "R7") (pin "1") (pinfunction "1_1") (pintype "passive"))
      (node (ref "SWR/CAL") (pin "2") (pinfunction "S_2") (pintype "passive"))
    )
    (net (code "146") (name "Net-(T1-B)") (class "Default")
      (node (ref "R12") (pin "2") (pinfunction "2_2") (pintype "passive"))
      (node (ref "T1") (pin "1") (pinfunction "B_1") (pintype "passive"))
    )
    (net (code "147") (name "Net-(T1-C)") (class "Default")
      (node (ref "T1") (pin "4") (pinfunction "C_4") (pintype "passive"))
      (node (ref "U1") (pin "3") (pinfunction "3_3") (pintype "passive"))
    )
    (net (code "148") (name "Net-(T4-B)") (class "Default")
      (node (ref "R15") (pin "1") (pinfunction "1_1") (pintype "passive"))
      (node (ref "T4") (pin "1") (pinfunction "B_1") (pintype "passive"))
    )
    (net (code "149") (name "Net-(T4-C)") (class "Default")
      (node (ref "R32") (pin "2") (pinfunction "2_2") (pintype "passive"))
      (node (ref "T4") (pin "4") (pinfunction "C_4") (pintype "passive"))
    )
    (net (code "150") (name "Net-(VOLUME-A)") (class "Default")
      (node (ref "U2") (pin "3") (pinfunction "3_3") (pintype "passive"))
      (node (ref "VOLUME") (pin "3") (pinfunction "A_3") (pintype "passive"))
    )
    (net (code "151") (name "Net-(VOLUME-E)") (class "Default")
      (node (ref "U2") (pin "2") (pinfunction "2_2") (pintype "passive"))
      (node (ref "VOLUME") (pin "1") (pinfunction "E_1") (pintype "passive"))
    )
    (net (code "152") (name "Net-(VOLUME-S)") (class "Default")
      (node (ref "U2") (pin "1") (pinfunction "1_1") (pintype "passive"))
      (node (ref "VOLUME") (pin "2") (pinfunction "S_2") (pintype "passive"))
    )
    (net (code "153") (name "VCC") (class "Default")
      (node (ref "5V") (pin "MP") (pinfunction "MP_MP") (pintype "passive"))
      (node (ref "C13") (pin "2") (pinfunction "2_2") (pintype "passive"))
      (node (ref "C14") (pin "2") (pinfunction "2_2") (pintype "passive"))
      (node (ref "C17") (pin "2") (pinfunction "2_2") (pintype "passive"))
      (node (ref "C23") (pin "2") (pinfunction "2_2") (pintype "passive"))
      (node (ref "C24") (pin "2") (pinfunction "2_2") (pintype "passive"))
      (node (ref "C35") (pin "2") (pinfunction "2_2") (pintype "passive"))
      (node (ref "C4") (pin "+") (pinfunction "+_+") (pintype "passive"))
      (node (ref "D2") (pin "C") (pinfunction "C_C") (pintype "passive"))
      (node (ref "IC3") (pin "28") (pinfunction "VCC_28") (pintype "bidirectional"))
      (node (ref "IC4") (pin "2") (pinfunction "A0_2") (pintype "bidirectional"))
      (node (ref "IC4") (pin "28") (pinfunction "VCC_28") (pintype "bidirectional"))
      (node (ref "IC5") (pin "21") (pinfunction "A0_21") (pintype "input"))
      (node (ref "IC5") (pin "24") (pinfunction "VDD_24") (pintype "power_in"))
      (node (ref "IC6") (pin "24") (pinfunction "VDD_24") (pintype "power_in"))
      (node (ref "IC8") (pin "14") (pinfunction "VDD_14") (pintype "power_in"))
      (node (ref "IC9") (pin "1") (pinfunction "WP_1") (pintype "bidirectional"))
      (node (ref "IC9") (pin "8") (pinfunction "VCC_8") (pintype "power_in"))
      (node (ref "R13") (pin "1") (pinfunction "1_1") (pintype "passive"))
      (node (ref "R21") (pin "1") (pinfunction "1_1") (pintype "passive"))
      (node (ref "R22") (pin "1") (pinfunction "1_1") (pintype "passive"))
      (node (ref "R26") (pin "2") (pinfunction "2_2") (pintype "passive"))
      (node (ref "R27") (pin "2") (pinfunction "2_2") (pintype "passive"))
      (node (ref "R33") (pin "1") (pinfunction "1_1") (pintype "passive"))
      (node (ref "R9") (pin "1") (pinfunction "1_1") (pintype "passive"))
      (node (ref "U3") (pin "1") (pinfunction "1_1") (pintype "passive"))
    )
    (net (code "154") (name "VCCMEM") (class "Default")
      (node (ref "C16") (pin "2") (pinfunction "2_2") (pintype "passive"))
      (node (ref "C8") (pin "2") (pinfunction "2_2") (pintype "passive"))
      (node (ref "D1") (pin "C") (pinfunction "C_C") (pintype "passive"))
      (node (ref "GC+") (pin "MP") (pinfunction "MP_MP") (pintype "passive"))
      (node (ref "IC1") (pin "21") (pinfunction "VCC_21") (pintype "power_in"))
      (node (ref "IC1") (pin "52") (pinfunction "VCC_52") (pintype "power_in"))
      (node (ref "IC7") (pin "3") (pinfunction "~{WP}_3") (pintype "input"))
      (node (ref "IC7") (pin "7") (pinfunction "~{HOLD}_7") (pintype "input"))
      (node (ref "IC7") (pin "8") (pinfunction "VCC_8") (pintype "power_in"))
      (node (ref "L1") (pin "2") (pinfunction "2_2") (pintype "passive"))
    )
    (net (code "155") (name "unconnected-(IC1-(A8)PC0-Pad35)") (class "Default")
      (node (ref "IC1") (pin "35") (pinfunction "(A8)PC0_35") (pintype "output"))
    )
    (net (code "156") (name "unconnected-(IC1-(A9)PC1-Pad36)") (class "Default")
      (node (ref "IC1") (pin "36") (pinfunction "(A9)PC1_36") (pintype "output"))
    )
    (net (code "157") (name "unconnected-(IC1-(A10)PC2-Pad37)") (class "Default")
      (node (ref "IC1") (pin "37") (pinfunction "(A10)PC2_37") (pintype "output"))
    )
    (net (code "158") (name "unconnected-(IC1-(A13)PC5-Pad40)") (class "Default")
      (node (ref "IC1") (pin "40") (pinfunction "(A13)PC5_40") (pintype "output"))
    )
    (net (code "159") (name "unconnected-(IC1-(A14)PC6-Pad41)") (class "Default")
      (node (ref "IC1") (pin "41") (pinfunction "(A14)PC6_41") (pintype "output"))
    )
    (net (code "160") (name "unconnected-(IC1-(A15)PC7-Pad42)") (class "Default")
      (node (ref "IC1") (pin "42") (pinfunction "(A15)PC7_42") (pintype "output"))
    )
    (net (code "161") (name "unconnected-(IC1-(AD0)PA0-Pad51)") (class "Default")
      (node (ref "IC1") (pin "51") (pinfunction "(AD0)PA0_51") (pintype "bidirectional"))
    )
    (net (code "162") (name "unconnected-(IC1-(AD1)PA1-Pad50)") (class "Default")
      (node (ref "IC1") (pin "50") (pinfunction "(AD1)PA1_50") (pintype "bidirectional"))
    )
    (net (code "163") (name "unconnected-(IC1-(IC1)PD4-Pad29)") (class "Default")
      (node (ref "IC1") (pin "29") (pinfunction "(IC1)PD4_29") (pintype "bidirectional"))
    )
    (net (code "164") (name "unconnected-(IC1-(OC0)PB4-Pad14)") (class "Default")
      (node (ref "IC1") (pin "14") (pinfunction "(OC0)PB4_14") (pintype "bidirectional"))
    )
    (net (code "165") (name "unconnected-(IC1-(OC1B)PB6-Pad16)") (class "Default")
      (node (ref "IC1") (pin "16") (pinfunction "(OC1B)PB6_16") (pintype "bidirectional"))
    )
    (net (code "166") (name "unconnected-(IC1-(OC2{slash}OC1C)PB7-Pad17)") (class "Default")
      (node (ref "IC1") (pin "17") (pinfunction "(OC2/OC1C)PB7_17") (pintype "bidirectional"))
    )
    (net (code "167") (name "unconnected-(IC1-(T1)PD6-Pad31)") (class "Default")
      (node (ref "IC1") (pin "31") (pinfunction "(T1)PD6_31") (pintype "bidirectional"))
    )
    (net (code "168") (name "unconnected-(IC1-(T2)PD7-Pad32)") (class "Default")
      (node (ref "IC1") (pin "32") (pinfunction "(T2)PD7_32") (pintype "bidirectional"))
    )
    (net (code "169") (name "unconnected-(IC1-(XCK0{slash}AIN0)PE2-Pad4)") (class "Default")
      (node (ref "IC1") (pin "4") (pinfunction "(XCK0/AIN0)PE2_4") (pintype "bidirectional"))
    )
    (net (code "170") (name "unconnected-(IC1-(XCK1)PD5-Pad30)") (class "Default")
      (node (ref "IC1") (pin "30") (pinfunction "(XCK1)PD5_30") (pintype "bidirectional"))
    )
    (net (code "171") (name "unconnected-(IC1-AREF-Pad62)") (class "Default")
      (node (ref "IC1") (pin "62") (pinfunction "AREF_62") (pintype "passive"))
    )
    (net (code "172") (name "unconnected-(IC1-PEN-Pad1)") (class "Default")
      (node (ref "IC1") (pin "1") (pinfunction "PEN_1") (pintype "input"))
    )
    (net (code "173") (name "unconnected-(IC1-PF2(ADC2)-Pad59)") (class "Default")
      (node (ref "IC1") (pin "59") (pinfunction "PF2(ADC2)_59") (pintype "input"))
    )
    (net (code "174") (name "unconnected-(IC1-PF3(ADC3)-Pad58)") (class "Default")
      (node (ref "IC1") (pin "58") (pinfunction "PF3(ADC3)_58") (pintype "input"))
    )
    (net (code "175") (name "unconnected-(IC1-PF4(ADC4{slash}TCK)-Pad57)") (class "Default")
      (node (ref "IC1") (pin "57") (pinfunction "PF4(ADC4/TCK)_57") (pintype "input"))
    )
    (net (code "176") (name "unconnected-(IC1-PF5(ADC5{slash}TMS)-Pad56)") (class "Default")
      (node (ref "IC1") (pin "56") (pinfunction "PF5(ADC5/TMS)_56") (pintype "input"))
    )
    (net (code "177") (name "unconnected-(IC1-PF6(ADC6{slash}TDO)-Pad55)") (class "Default")
      (node (ref "IC1") (pin "55") (pinfunction "PF6(ADC6/TDO)_55") (pintype "input"))
    )
    (net (code "178") (name "unconnected-(IC1-PF7(ADC7{slash}TDI)-Pad54)") (class "Default")
      (node (ref "IC1") (pin "54") (pinfunction "PF7(ADC7/TDI)_54") (pintype "input"))
    )
    (net (code "179") (name "unconnected-(IC1-PG0(WR)-Pad33)") (class "Default")
      (node (ref "IC1") (pin "33") (pinfunction "PG0(WR)_33") (pintype "bidirectional"))
    )
    (net (code "180") (name "unconnected-(IC1-PG1(RD)-Pad34)") (class "Default")
      (node (ref "IC1") (pin "34") (pinfunction "PG1(RD)_34") (pintype "bidirectional"))
    )
    (net (code "181") (name "unconnected-(IC1-PG2(ALE)-Pad43)") (class "Default")
      (node (ref "IC1") (pin "43") (pinfunction "PG2(ALE)_43") (pintype "bidirectional"))
    )
    (net (code "182") (name "unconnected-(IC1-PG3(TOSC2)-Pad18)") (class "Default")
      (node (ref "IC1") (pin "18") (pinfunction "PG3(TOSC2)_18") (pintype "bidirectional"))
    )
    (net (code "183") (name "unconnected-(IC1-PG4(TOSC1)-Pad19)") (class "Default")
      (node (ref "IC1") (pin "19") (pinfunction "PG4(TOSC1)_19") (pintype "bidirectional"))
    )
    (net (code "184") (name "unconnected-(IC3-{slash}OUT12-Pad20)") (class "Default")
      (node (ref "IC3") (pin "20") (pinfunction "/OUT12_20") (pintype "bidirectional"))
    )
    (net (code "185") (name "unconnected-(IC3-{slash}OUT13-Pad21)") (class "Default")
      (node (ref "IC3") (pin "21") (pinfunction "/OUT13_21") (pintype "bidirectional"))
    )
    (net (code "186") (name "unconnected-(IC3-{slash}OUT14-Pad22)") (class "Default")
      (node (ref "IC3") (pin "22") (pinfunction "/OUT14_22") (pintype "bidirectional"))
    )
    (net (code "187") (name "unconnected-(IC3-{slash}OUT15-Pad23)") (class "Default")
      (node (ref "IC3") (pin "23") (pinfunction "/OUT15_23") (pintype "bidirectional"))
    )
    (net (code "188") (name "unconnected-(IC4-{slash}OUT12-Pad20)") (class "Default")
      (node (ref "IC4") (pin "20") (pinfunction "/OUT12_20") (pintype "bidirectional"))
    )
    (net (code "189") (name "unconnected-(IC4-{slash}OUT13-Pad21)") (class "Default")
      (node (ref "IC4") (pin "21") (pinfunction "/OUT13_21") (pintype "bidirectional"))
    )
    (net (code "190") (name "unconnected-(IC4-{slash}OUT14-Pad22)") (class "Default")
      (node (ref "IC4") (pin "22") (pinfunction "/OUT14_22") (pintype "bidirectional"))
    )
    (net (code "191") (name "unconnected-(IC4-{slash}OUT15-Pad23)") (class "Default")
      (node (ref "IC4") (pin "23") (pinfunction "/OUT15_23") (pintype "bidirectional"))
    )
    (net (code "192") (name "unconnected-(IC5-I{slash}O0.3-Pad7)") (class "Default")
      (node (ref "IC5") (pin "7") (pinfunction "I/O0.3_7") (pintype "bidirectional"))
    )
    (net (code "193") (name "unconnected-(IC5-I{slash}O0.4-Pad8)") (class "Default")
      (node (ref "IC5") (pin "8") (pinfunction "I/O0.4_8") (pintype "bidirectional"))
    )
    (net (code "194") (name "unconnected-(IC5-I{slash}O0.5-Pad9)") (class "Default")
      (node (ref "IC5") (pin "9") (pinfunction "I/O0.5_9") (pintype "bidirectional"))
    )
    (net (code "195") (name "unconnected-(IC6-I{slash}O0.7-Pad11)") (class "Default")
      (node (ref "IC6") (pin "11") (pinfunction "I/O0.7_11") (pintype "bidirectional"))
    )
    (net (code "196") (name "unconnected-(IC6-I{slash}O1.5-Pad18)") (class "Default")
      (node (ref "IC6") (pin "18") (pinfunction "I/O1.5_18") (pintype "bidirectional"))
    )
    (net (code "197") (name "unconnected-(IC6-I{slash}O1.6-Pad19)") (class "Default")
      (node (ref "IC6") (pin "19") (pinfunction "I/O1.6_19") (pintype "bidirectional"))
    )
    (net (code "198") (name "unconnected-(IC6-I{slash}O1.7-Pad20)") (class "Default")
      (node (ref "IC6") (pin "20") (pinfunction "I/O1.7_20") (pintype "bidirectional"))
    )
    (net (code "199") (name "unconnected-(IC8-BP3-Pad28)") (class "Default")
      (node (ref "IC8") (pin "28") (pinfunction "BP3_28") (pintype "output"))
    )
    (net (code "200") (name "unconnected-(IC8-CLK-Pad13)") (class "Default")
      (node (ref "IC8") (pin "13") (pinfunction "CLK_13") (pintype "bidirectional"))
    )
    (net (code "201") (name "unconnected-(IC8-S33-Pad64)") (class "Default")
      (node (ref "IC8") (pin "64") (pinfunction "S33_64") (pintype "output"))
    )
    (net (code "202") (name "unconnected-(IC8-S34-Pad2)") (class "Default")
      (node (ref "IC8") (pin "2") (pinfunction "S34_2") (pintype "output"))
    )
    (net (code "203") (name "unconnected-(IC8-S35-Pad3)") (class "Default")
      (node (ref "IC8") (pin "3") (pinfunction "S35_3") (pintype "output"))
    )
    (net (code "204") (name "unconnected-(IC8-S36-Pad4)") (class "Default")
      (node (ref "IC8") (pin "4") (pinfunction "S36_4") (pintype "output"))
    )
    (net (code "205") (name "unconnected-(IC8-S37-Pad5)") (class "Default")
      (node (ref "IC8") (pin "5") (pinfunction "S37_5") (pintype "output"))
    )
    (net (code "206") (name "unconnected-(IC8-S38-Pad6)") (class "Default")
      (node (ref "IC8") (pin "6") (pinfunction "S38_6") (pintype "output"))
    )
    (net (code "207") (name "unconnected-(IC8-S39-Pad7)") (class "Default")
      (node (ref "IC8") (pin "7") (pinfunction "S39_7") (pintype "output"))
    )
    (net (code "208") (name "unconnected-(IC8-SYNC-Pad12)") (class "Default")
      (node (ref "IC8") (pin "12") (pinfunction "SYNC_12") (pintype "bidirectional"))
    )
    (net (code "209") (name "unconnected-(RF-POWER-A-Pad3)") (class "Default")
      (node (ref "RF-POWER") (pin "3") (pinfunction "A_3") (pintype "passive"))
    )
  )
)
